# VCU.net
KiCad netlist of a schematic drawn in EAGLE
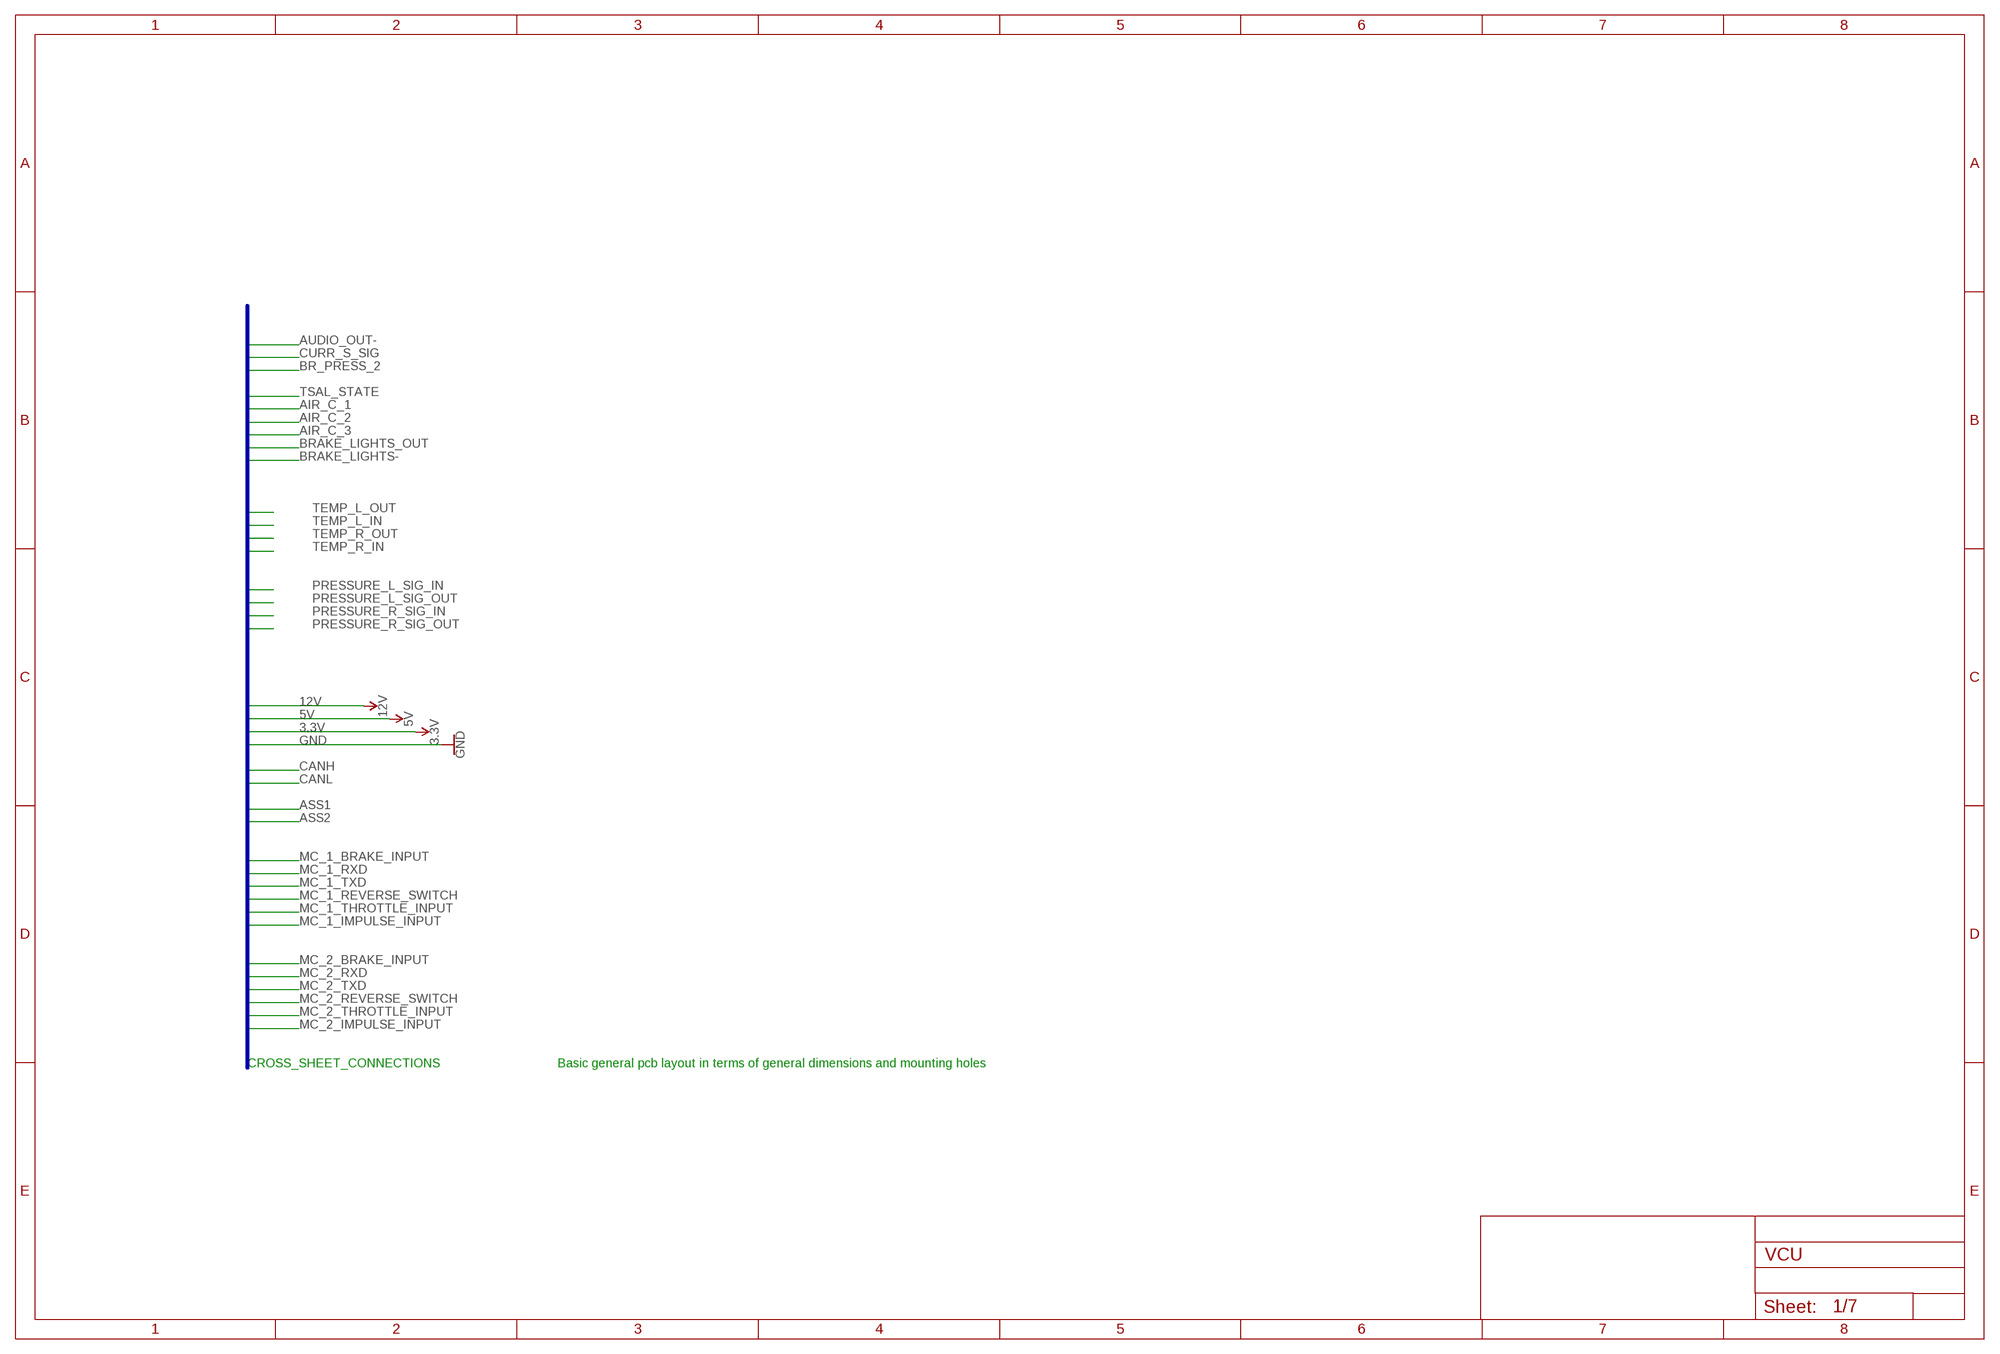
[diagram p0: schematic, sheet 1]
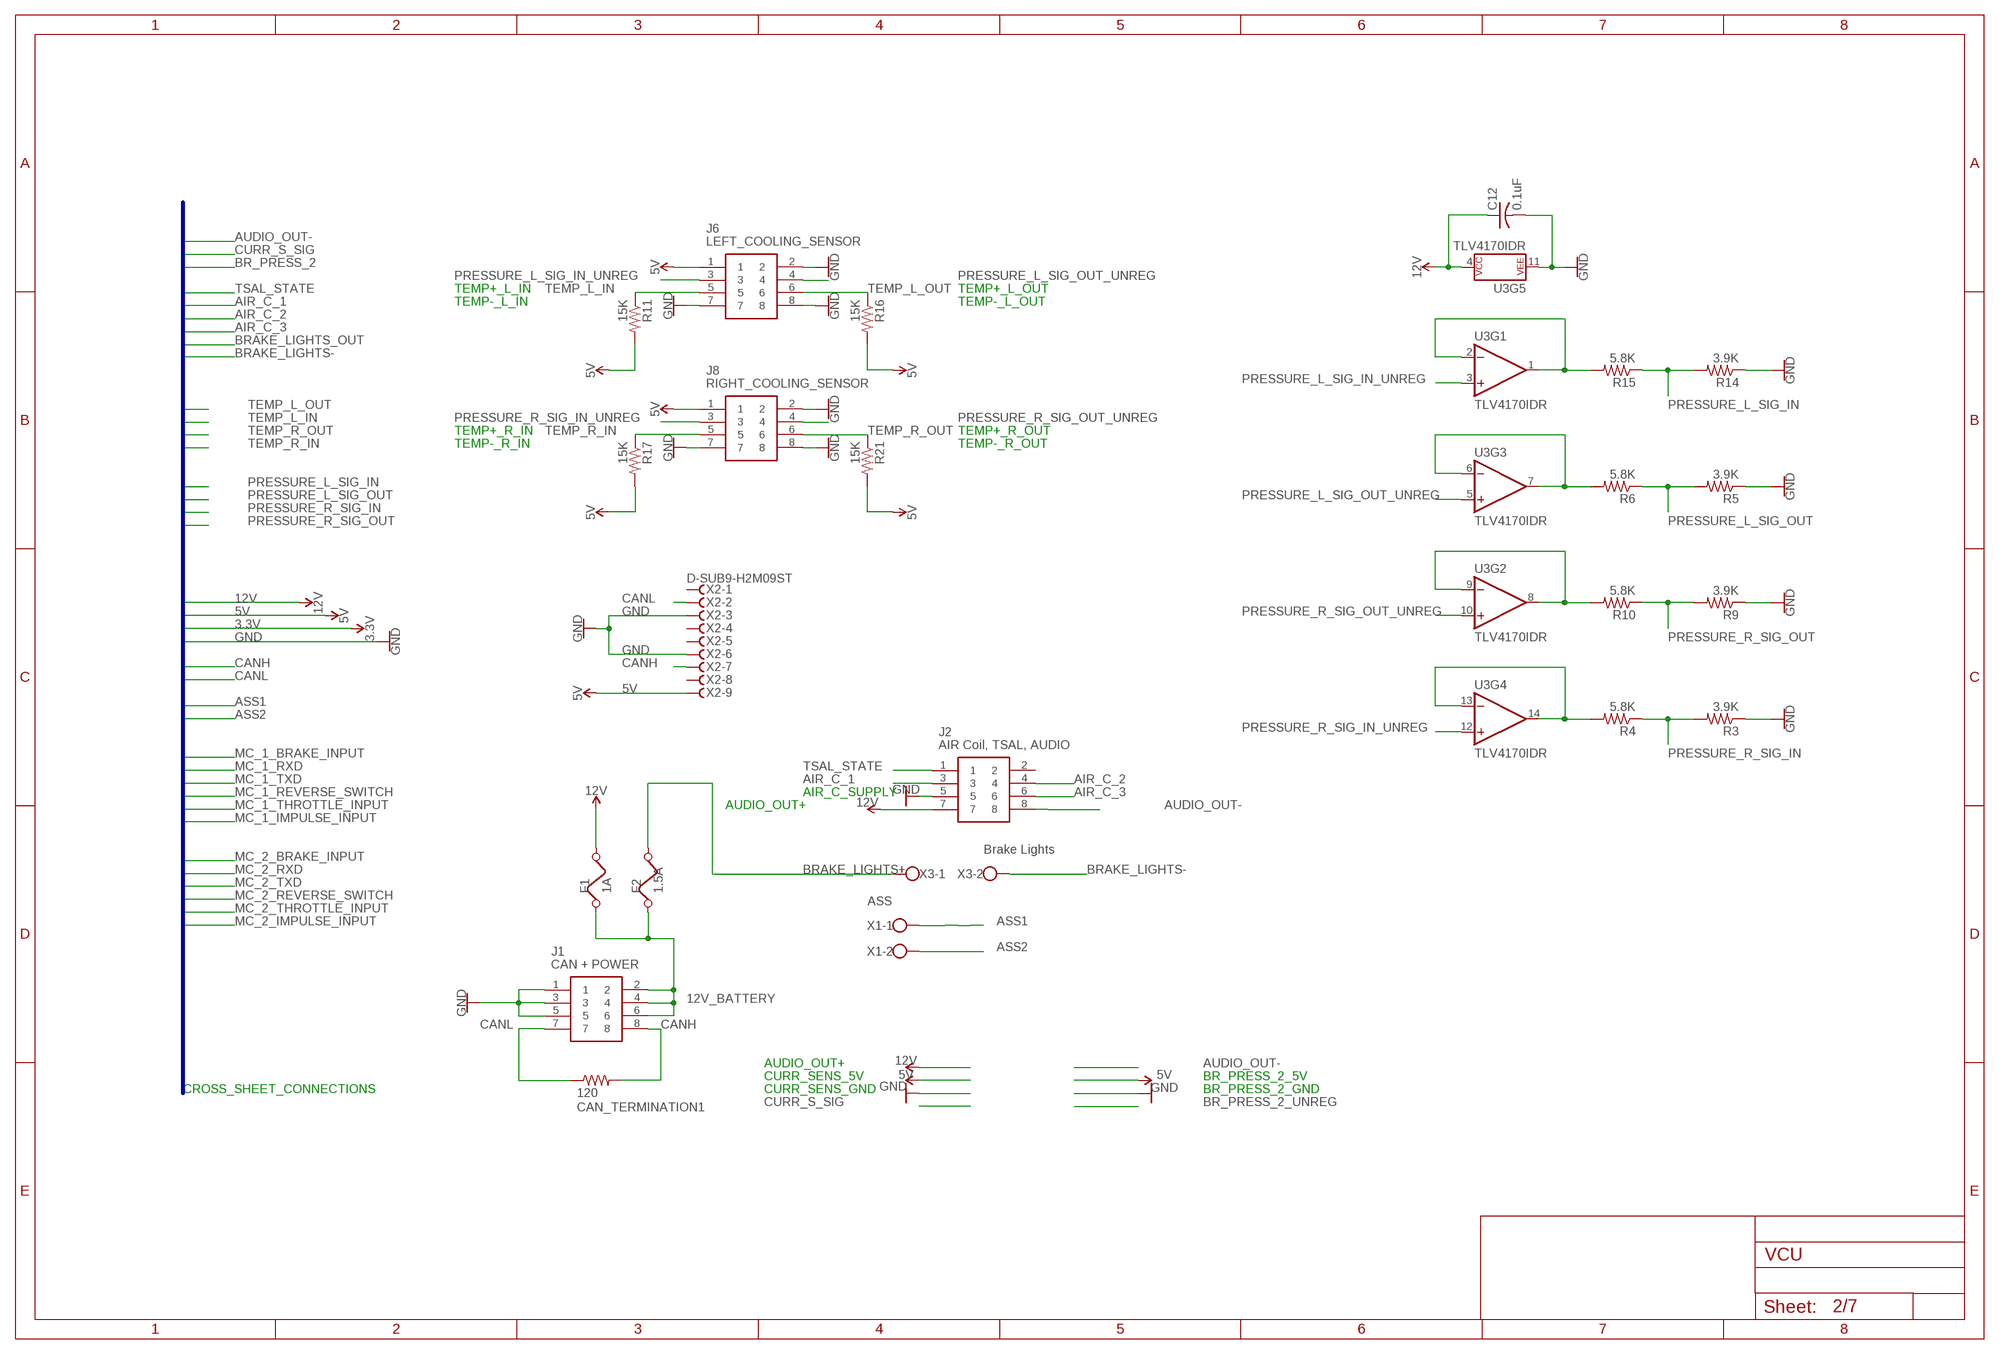
[diagram p1: schematic, sheet 2]
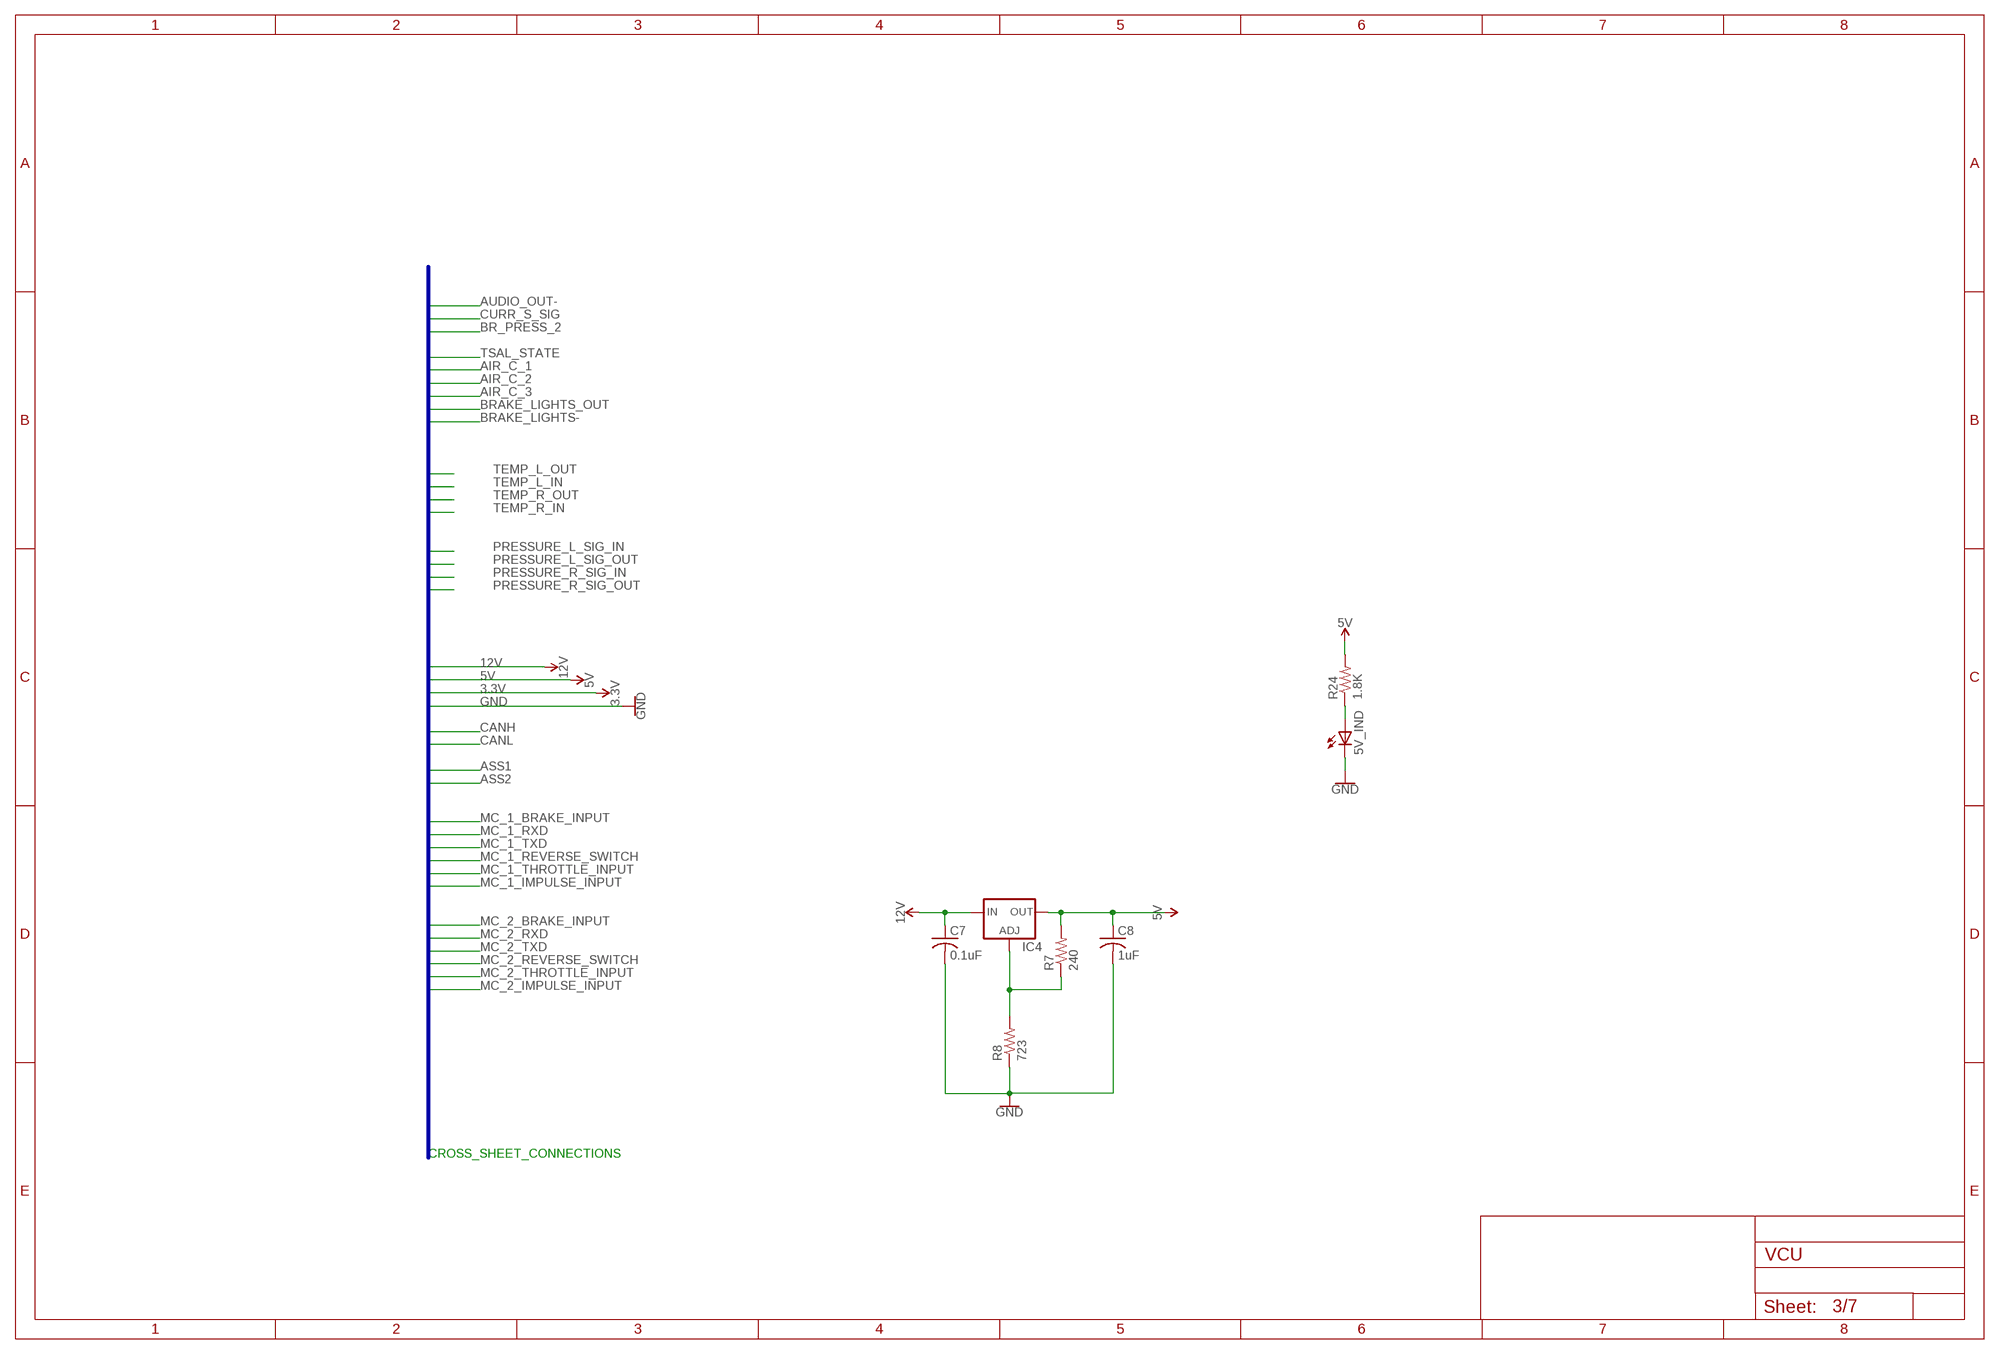
[diagram p2: schematic, sheet 3]
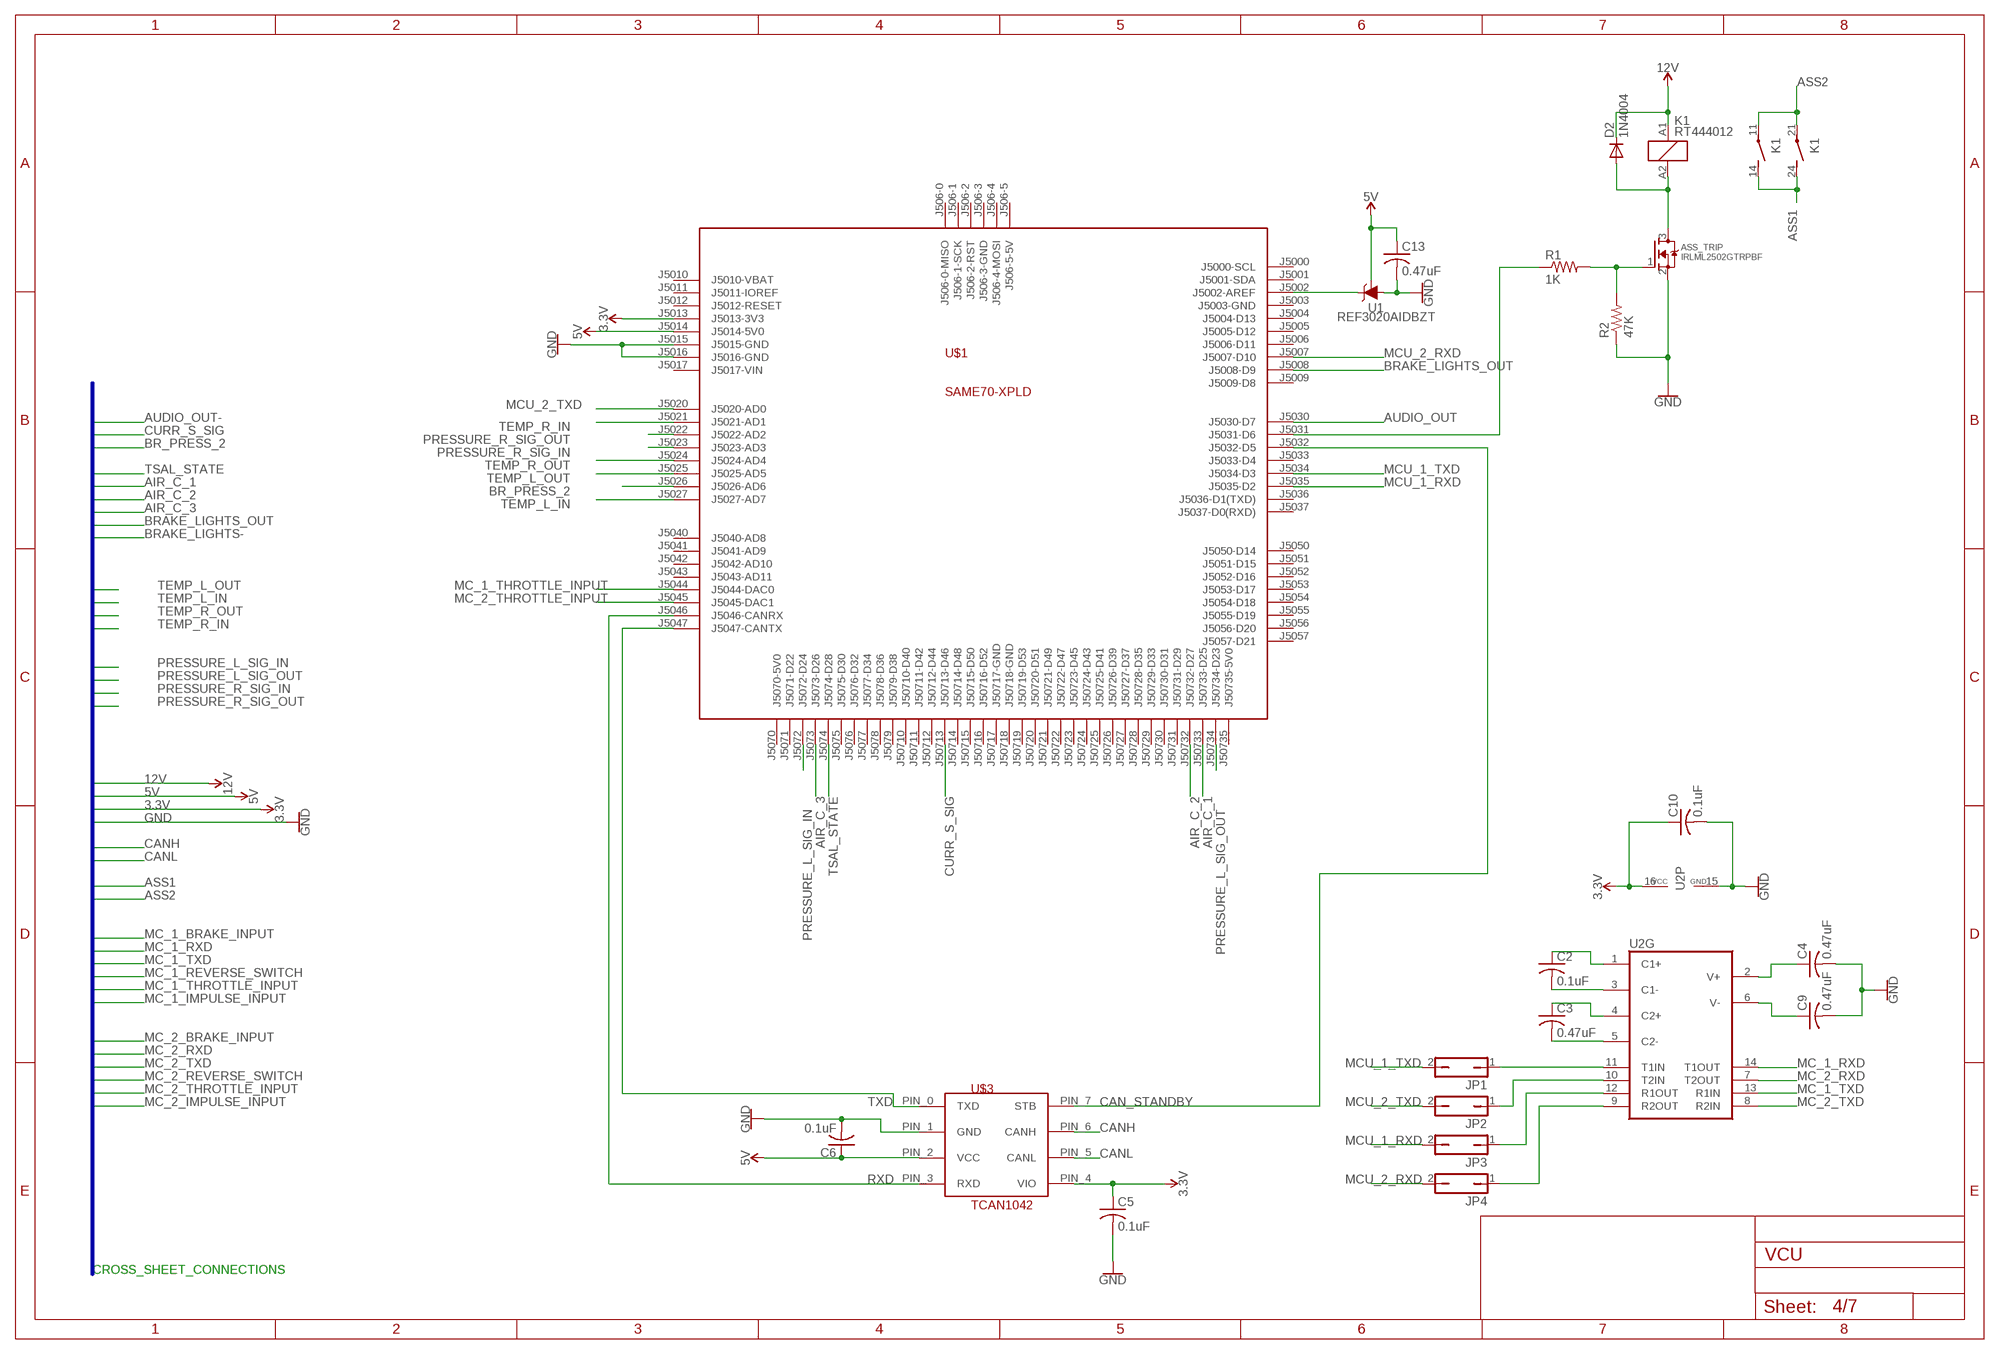
[diagram p3: schematic, sheet 4]
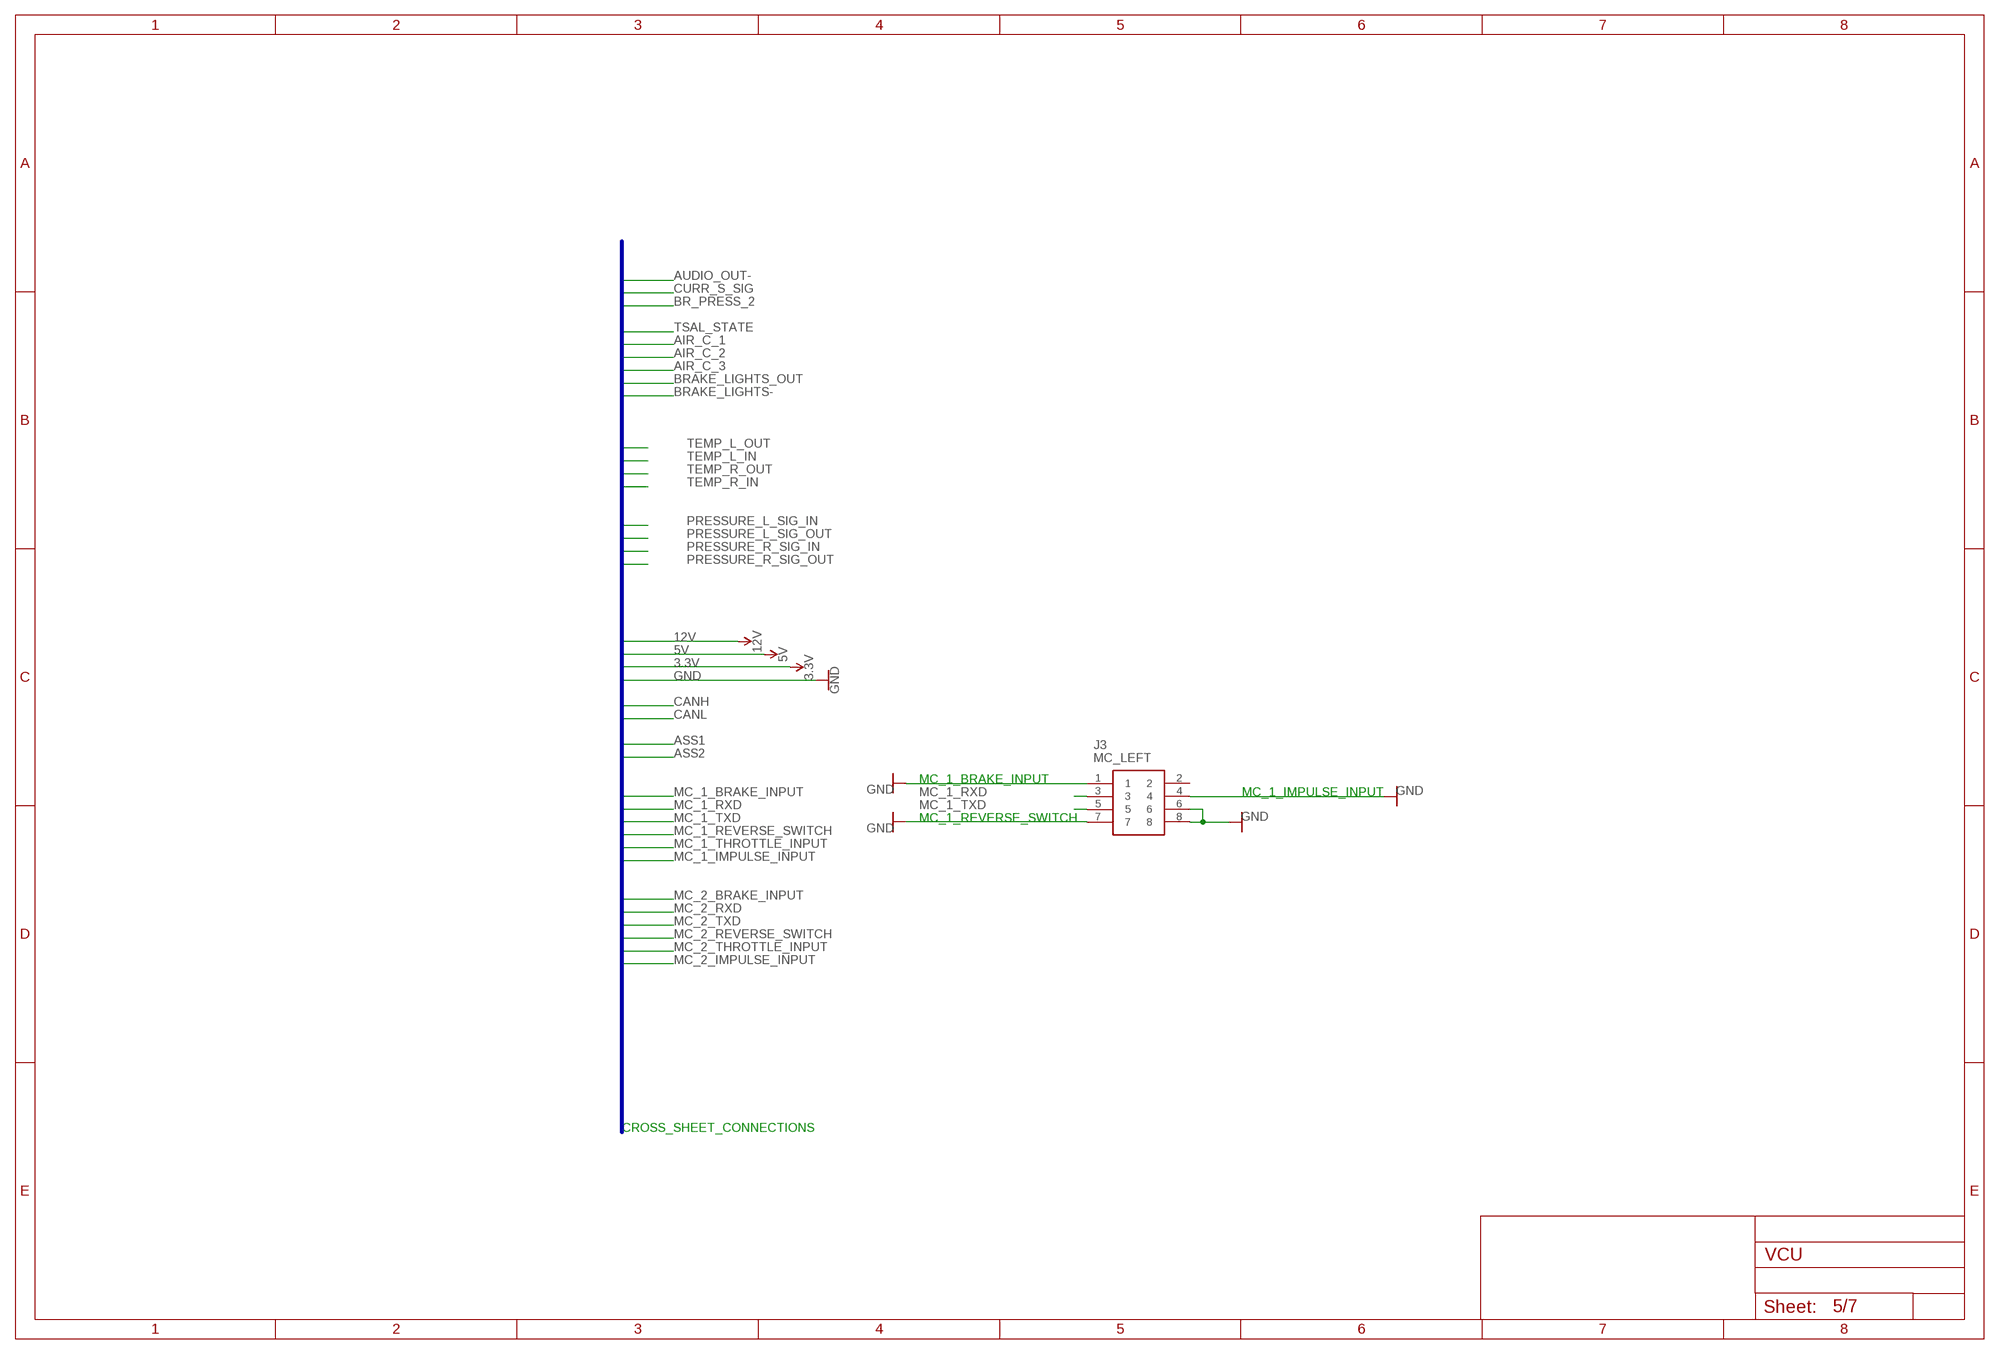
[diagram p4: schematic, sheet 5]
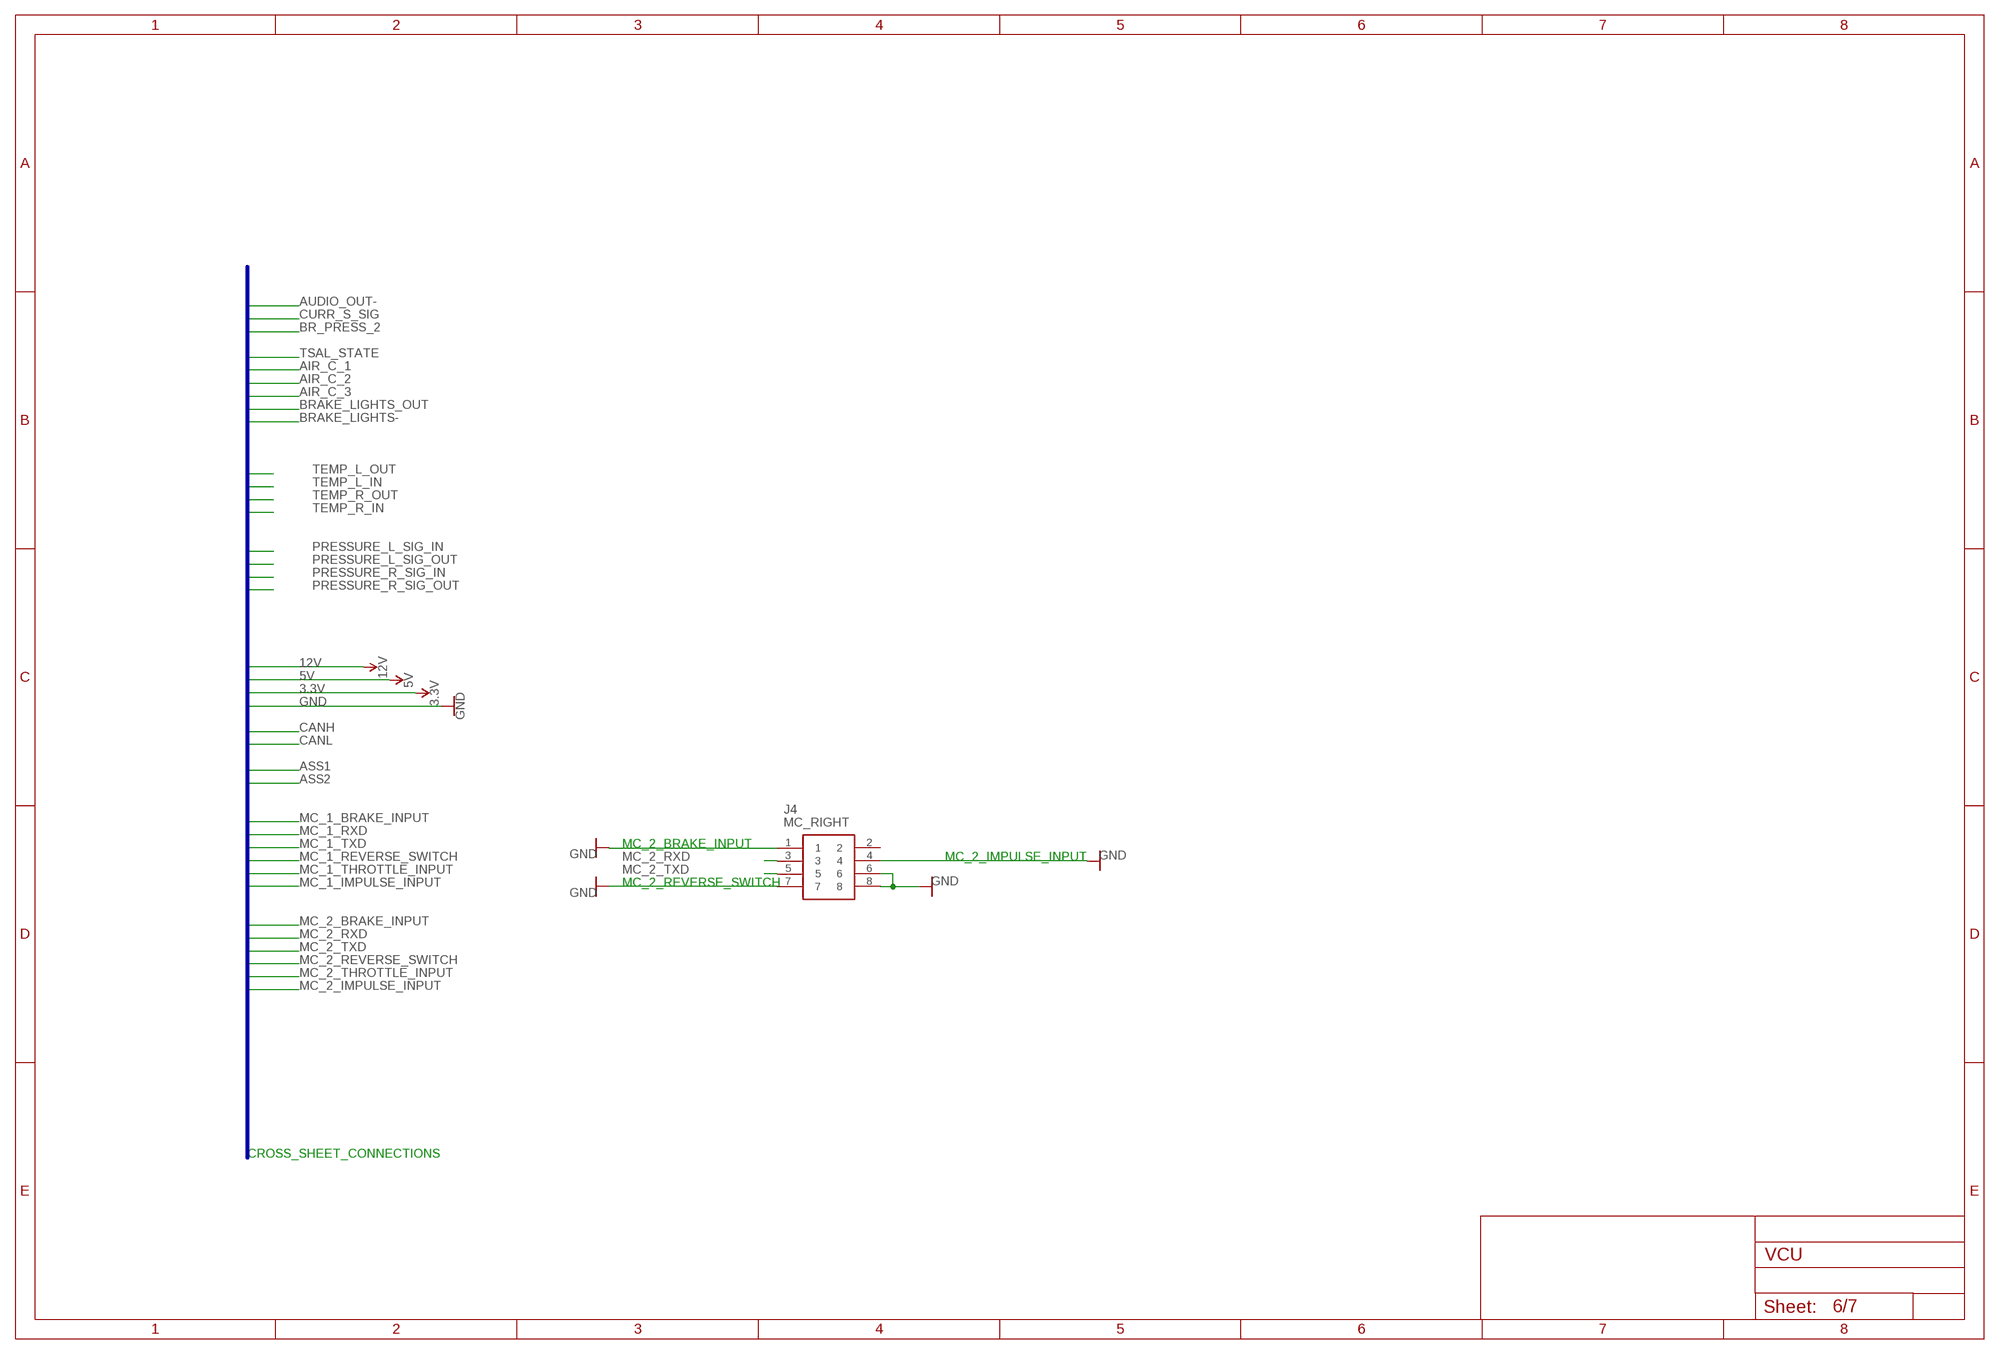
[diagram p5: schematic, sheet 6]
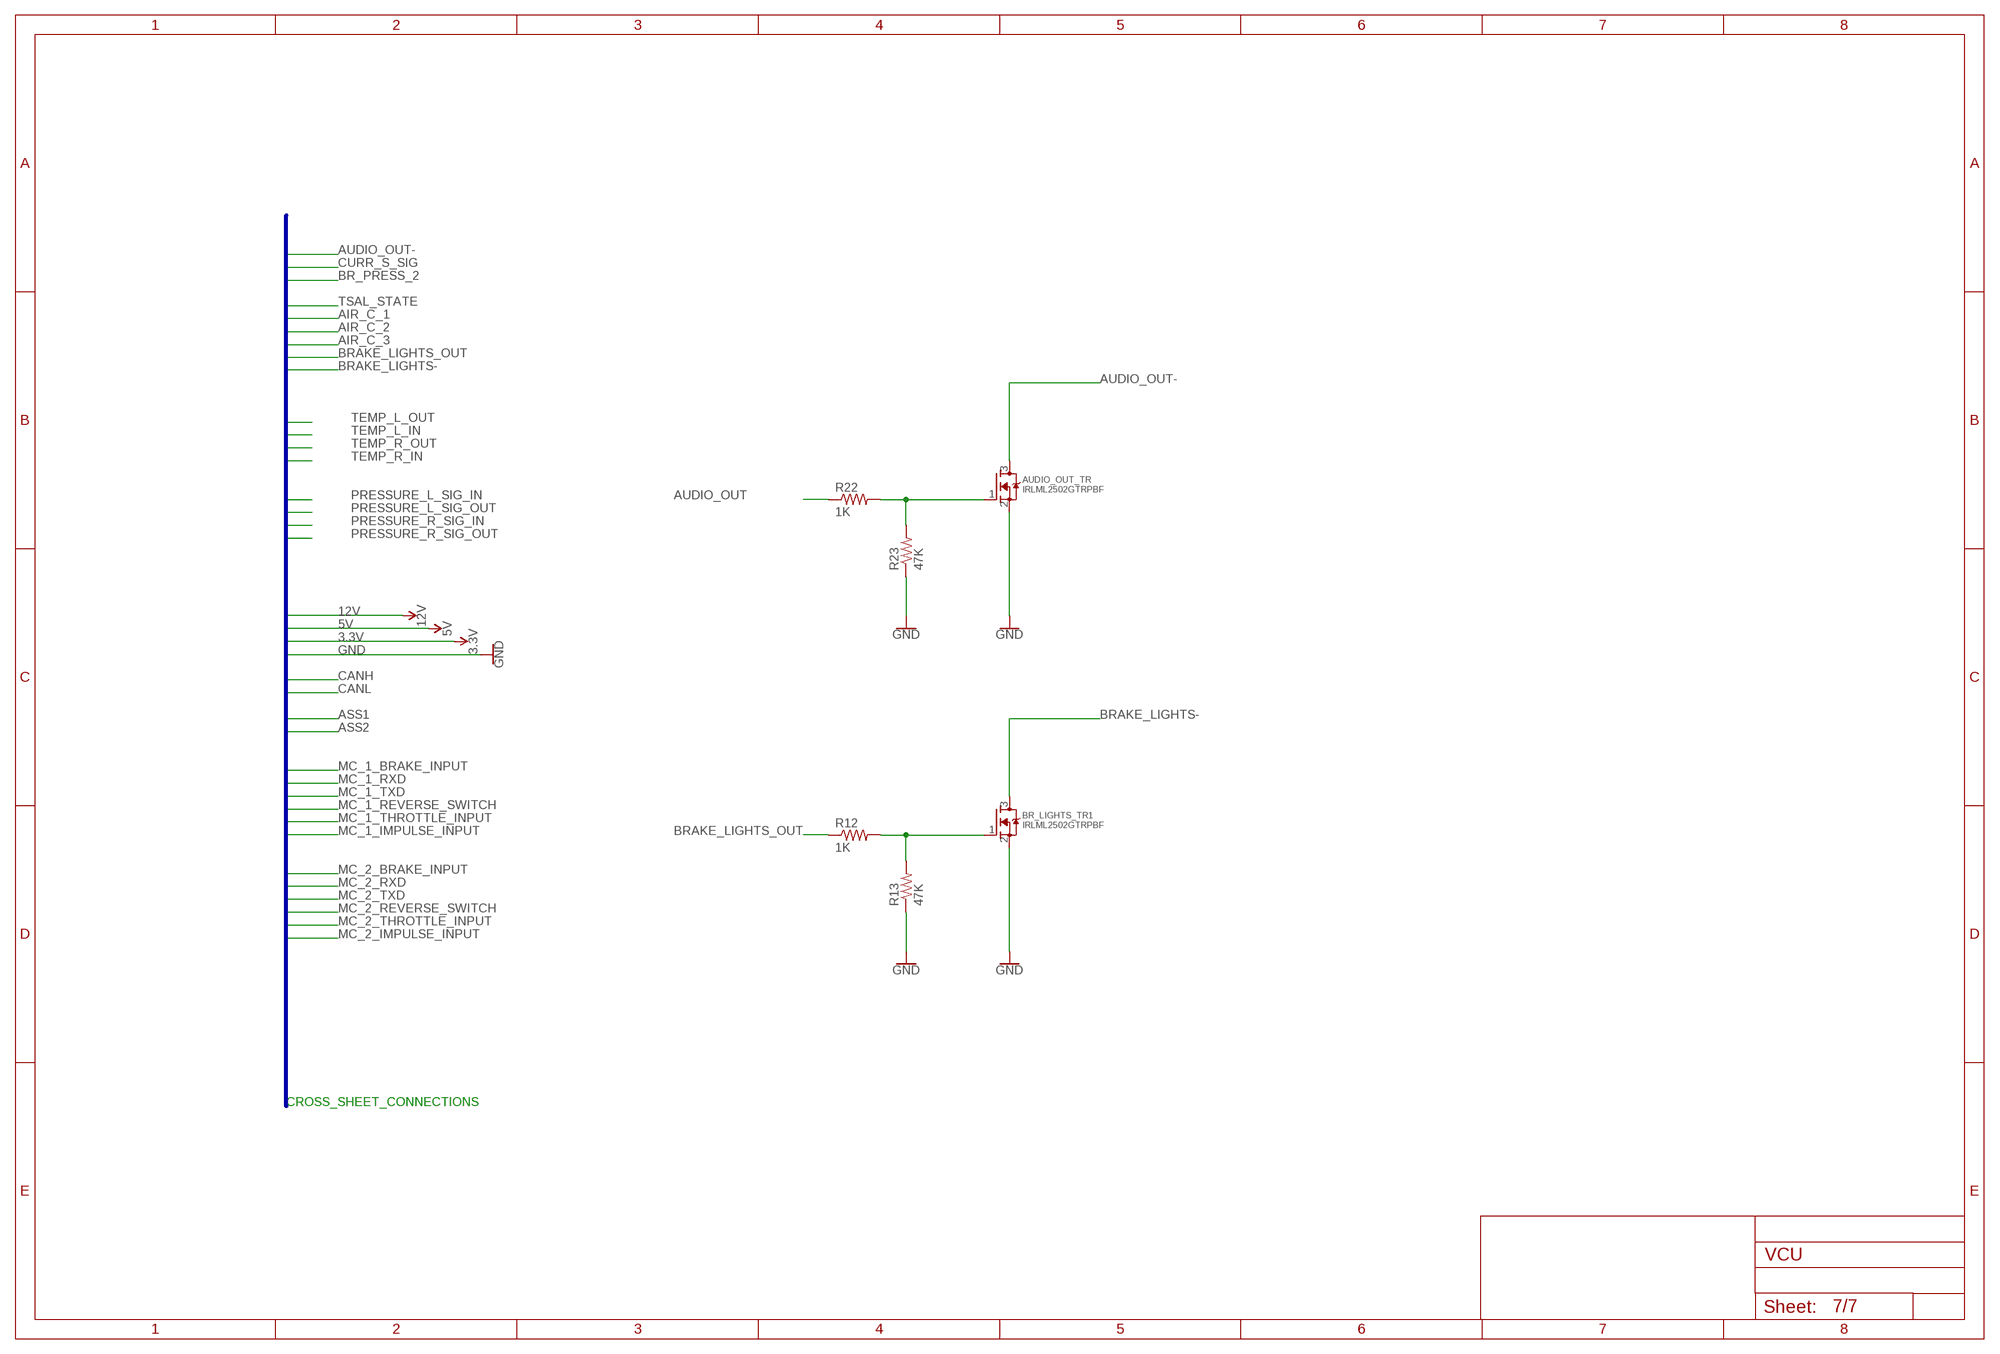
[diagram p6: schematic, sheet 7]

(export (version "E")
  (design (tool "Eeschema 10.0.6"))
  (components
    (comp (ref "ASS_TRIP")
      (value "IRLML2502GTRPBF")
      (footprint "eagle-import:SOT23")
      (libsource (lib "eagle-import") (part "MOSFET-NREFLOW"))
    )
    (comp (ref "C2")
      (value "0.1uF")
      (footprint "eagle-import:C025-024X044")
      (libsource (lib "eagle-import") (part "C-US025-024X044"))
    )
    (comp (ref "C3")
      (value "0.47uF")
      (footprint "eagle-import:C025-024X044")
      (libsource (lib "eagle-import") (part "C-US025-024X044"))
    )
    (comp (ref "C4")
      (value "0.47uF")
      (footprint "eagle-import:C025-024X044")
      (libsource (lib "eagle-import") (part "C-US025-024X044"))
    )
    (comp (ref "C5")
      (value "0.1uF")
      (footprint "eagle-import:C025-024X044")
      (libsource (lib "eagle-import") (part "C-US025-024X044"))
    )
    (comp (ref "C6")
      (value "0.1uF")
      (footprint "eagle-import:C025-024X044")
      (libsource (lib "eagle-import") (part "C-US025-024X044"))
    )
    (comp (ref "C9")
      (value "0.47uF")
      (footprint "eagle-import:C025-024X044")
      (libsource (lib "eagle-import") (part "C-US025-024X044"))
    )
    (comp (ref "C10")
      (value "0.1uF")
      (footprint "eagle-import:C025-024X044")
      (libsource (lib "eagle-import") (part "C-US025-024X044"))
    )
    (comp (ref "C13")
      (value "0.47uF")
      (footprint "eagle-import:C050-024X044")
      (libsource (lib "eagle-import") (part "C-US050-024X044"))
    )
    (comp (ref "D2")
      (value "1N4004")
      (footprint "eagle-import:DO41-10")
      (libsource (lib "eagle-import") (part "1N4004"))
    )
    (comp (ref "JP1")
      (value "JP1Q")
      (footprint "eagle-import:JP1")
      (libsource (lib "eagle-import") (part "JP1Q"))
    )
    (comp (ref "JP2")
      (value "JP1Q")
      (footprint "eagle-import:JP1")
      (libsource (lib "eagle-import") (part "JP1Q"))
    )
    (comp (ref "JP3")
      (value "JP1Q")
      (footprint "eagle-import:JP1")
      (libsource (lib "eagle-import") (part "JP1Q"))
    )
    (comp (ref "JP4")
      (value "JP1Q")
      (footprint "eagle-import:JP1")
      (libsource (lib "eagle-import") (part "JP1Q"))
    )
    (comp (ref "K1")
      (value "RT444012")
      (footprint "eagle-import:RT2N_O")
      (libsource (lib "eagle-import") (part "RT44?4012"))
    )
    (comp (ref "R1")
      (value "1K")
      (footprint "eagle-import:R0805")
      (libsource (lib "eagle-import") (part "R-US_R0805"))
    )
    (comp (ref "R2")
      (value "47K")
      (footprint "eagle-import:R0805")
      (libsource (lib "eagle-import") (part "R-US_R0805"))
    )
    (comp (ref "U$1")
      (value "SAME70-XPLD")
      (footprint "eagle-import:SAME70-XPLD")
      (libsource (lib "eagle-import") (part "SAME70-XPLD"))
    )
    (comp (ref "U$3")
      (value "TCAN1042")
      (footprint "eagle-import:TCAN1042")
      (libsource (lib "eagle-import") (part "TCAN1042"))
    )
    (comp (ref "U1")
      (value "REF3020AIDBZT")
      (footprint "eagle-import:SOT23-3")
      (libsource (lib "eagle-import") (part "LM4051"))
    )
    (comp (ref "U2")
      (value "MAX3232S")
      (footprint "eagle-import:SO16")
      (libsource (lib "eagle-import") (part "MAX3232S"))
    )
    (comp (ref "J4")
      (value "MC_RIGHT")
      (footprint "eagle-import:HDRV8W64P254_2X4_1778X895X915P")
      (fields
        (field (name "MANUFACTURER_PART_NUMBER") "T821108A1S100CEU")
        (field (name "RS_PART_NUMBER") "1702738")
      )
      (libsource (lib "eagle-import") (part "T821108A1S100CEU"))
    )
    (comp (ref "AUDIO_OUT_TR")
      (value "IRLML2502GTRPBF")
      (footprint "eagle-import:SOT23")
      (libsource (lib "eagle-import") (part "MOSFET-NREFLOW"))
    )
    (comp (ref "BR_LIGHTS_TR1")
      (value "IRLML2502GTRPBF")
      (footprint "eagle-import:SOT23")
      (libsource (lib "eagle-import") (part "MOSFET-NREFLOW"))
    )
    (comp (ref "R12")
      (value "1K")
      (footprint "eagle-import:R0805")
      (libsource (lib "eagle-import") (part "R-US_R0805"))
    )
    (comp (ref "R13")
      (value "47K")
      (footprint "eagle-import:R0805")
      (libsource (lib "eagle-import") (part "R-US_R0805"))
    )
    (comp (ref "R22")
      (value "1K")
      (footprint "eagle-import:R0805")
      (libsource (lib "eagle-import") (part "R-US_R0805"))
    )
    (comp (ref "R23")
      (value "47K")
      (footprint "eagle-import:R0805")
      (libsource (lib "eagle-import") (part "R-US_R0805"))
    )
    (comp (ref "J3")
      (value "MC_LEFT")
      (footprint "eagle-import:HDRV8W64P254_2X4_1778X895X915P")
      (fields
        (field (name "MANUFACTURER_PART_NUMBER") "T821108A1S100CEU")
        (field (name "RS_PART_NUMBER") "1702738")
      )
      (libsource (lib "eagle-import") (part "T821108A1S100CEU"))
    )
    (comp (ref "C12")
      (value "0.1uF")
      (footprint "eagle-import:C050-024X044")
      (libsource (lib "eagle-import") (part "C-US050-024X044"))
    )
    (comp (ref "CAN_TERMINATION1")
      (value "120")
      (footprint "eagle-import:R0805")
      (libsource (lib "eagle-import") (part "R-US_R0805"))
    )
    (comp (ref "F1")
      (value "1A")
      (footprint "eagle-import:FUSE")
      (libsource (lib "eagle-import") (part "FUSE"))
    )
    (comp (ref "F2")
      (value "1.5A")
      (footprint "eagle-import:FUSE")
      (libsource (lib "eagle-import") (part "FUSE"))
    )
    (comp (ref "J1")
      (value "CAN + POWER")
      (footprint "eagle-import:HDRV8W64P254_2X4_1778X895X915P")
      (fields
        (field (name "MANUFACTURER_PART_NUMBER") "T821108A1S100CEU")
        (field (name "RS_PART_NUMBER") "1702738")
      )
      (libsource (lib "eagle-import") (part "T821108A1S100CEU"))
    )
    (comp (ref "J2")
      (value "AIR Coil, TSAL, AUDIO")
      (footprint "eagle-import:HDRV8W64P254_2X4_1778X895X915P")
      (fields
        (field (name "MANUFACTURER_PART_NUMBER") "T821108A1S100CEU")
        (field (name "RS_PART_NUMBER") "1702738")
      )
      (libsource (lib "eagle-import") (part "T821108A1S100CEU"))
    )
    (comp (ref "J6")
      (value "LEFT_COOLING_SENSOR")
      (footprint "eagle-import:HDRV8W64P254_2X4_1778X895X915P")
      (fields
        (field (name "MANUFACTURER_PART_NUMBER") "T821108A1S100CEU")
        (field (name "RS_PART_NUMBER") "1702738")
      )
      (libsource (lib "eagle-import") (part "T821108A1S100CEU"))
    )
    (comp (ref "J8")
      (value "RIGHT_COOLING_SENSOR")
      (footprint "eagle-import:HDRV8W64P254_2X4_1778X895X915P")
      (fields
        (field (name "MANUFACTURER_PART_NUMBER") "T821108A1S100CEU")
        (field (name "RS_PART_NUMBER") "1702738")
      )
      (libsource (lib "eagle-import") (part "T821108A1S100CEU"))
    )
    (comp (ref "R3")
      (value "3.9K")
      (footprint "eagle-import:R0805")
      (libsource (lib "eagle-import") (part "R-US_R0805"))
    )
    (comp (ref "R4")
      (value "5.8K")
      (footprint "eagle-import:R0805")
      (libsource (lib "eagle-import") (part "R-US_R0805"))
    )
    (comp (ref "R5")
      (value "3.9K")
      (footprint "eagle-import:R0805")
      (libsource (lib "eagle-import") (part "R-US_R0805"))
    )
    (comp (ref "R6")
      (value "5.8K")
      (footprint "eagle-import:R0805")
      (libsource (lib "eagle-import") (part "R-US_R0805"))
    )
    (comp (ref "R9")
      (value "3.9K")
      (footprint "eagle-import:R0805")
      (libsource (lib "eagle-import") (part "R-US_R0805"))
    )
    (comp (ref "R10")
      (value "5.8K")
      (footprint "eagle-import:R0805")
      (libsource (lib "eagle-import") (part "R-US_R0805"))
    )
    (comp (ref "R11")
      (value "15K")
      (footprint "eagle-import:R0805")
      (libsource (lib "eagle-import") (part "R-US_R0805"))
    )
    (comp (ref "R14")
      (value "3.9K")
      (footprint "eagle-import:R0805")
      (libsource (lib "eagle-import") (part "R-US_R0805"))
    )
    (comp (ref "R15")
      (value "5.8K")
      (footprint "eagle-import:R0805")
      (libsource (lib "eagle-import") (part "R-US_R0805"))
    )
    (comp (ref "R16")
      (value "15K")
      (footprint "eagle-import:R0805")
      (libsource (lib "eagle-import") (part "R-US_R0805"))
    )
    (comp (ref "R17")
      (value "15K")
      (footprint "eagle-import:R0805")
      (libsource (lib "eagle-import") (part "R-US_R0805"))
    )
    (comp (ref "R21")
      (value "15K")
      (footprint "eagle-import:R0805")
      (libsource (lib "eagle-import") (part "R-US_R0805"))
    )
    (comp (ref "U3")
      (value "TLV4170IDR")
      (footprint "eagle-import:SO14")
      (libsource (lib "eagle-import") (part "LMV324"))
    )
    (comp (ref "X1")
      (value "ASS")
      (footprint "eagle-import:W237-102")
      (fields (field (name "MPN") "237-102"))
      (libsource (lib "eagle-import") (part "W237-102"))
    )
    (comp (ref "X2")
      (value "D-SUB9-H2M09ST")
      (footprint "eagle-import:H2M09ST")
      (libsource (lib "eagle-import") (part "D-SUB9-H2M09ST"))
    )
    (comp (ref "X3")
      (value "Brake Lights")
      (footprint "eagle-import:W237-102")
      (fields (field (name "MPN") "237-102"))
      (libsource (lib "eagle-import") (part "W237-102"))
    )
    (comp (ref "5V_IND")
      (value "LED3MM")
      (footprint "eagle-import:LED3MM")
      (libsource (lib "eagle-import") (part "LED3MM"))
    )
    (comp (ref "C7")
      (value "0.1uF")
      (footprint "eagle-import:C050-025X075")
      (libsource (lib "eagle-import") (part "C-US050-025X075"))
    )
    (comp (ref "C8")
      (value "1uF")
      (footprint "eagle-import:C050-025X075")
      (libsource (lib "eagle-import") (part "C-US050-025X075"))
    )
    (comp (ref "IC4")
      (value "LM317TS")
      (footprint "eagle-import:317TS")
      (libsource (lib "eagle-import") (part "LM317TS"))
    )
    (comp (ref "R7")
      (value "240")
      (footprint "eagle-import:R0805")
      (libsource (lib "eagle-import") (part "R-US_R0805"))
    )
    (comp (ref "R8")
      (value "723")
      (footprint "eagle-import:R0805")
      (libsource (lib "eagle-import") (part "R-US_R0805"))
    )
    (comp (ref "R24")
      (value "1.8K")
      (footprint "eagle-import:R0805")
      (libsource (lib "eagle-import") (part "R-US_R0805"))
    )
  )
  (nets
    (net (code "1") (name "3.3V") (class "Default")
      (node (ref "C10") (pin "1") (pinfunction "1_1") (pintype "passive"))
      (node (ref "C5") (pin "1") (pinfunction "1_1") (pintype "passive"))
      (node (ref "U$1") (pin "J5013") (pinfunction "J5013-3V3_J5013") (pintype "bidirectional"))
      (node (ref "U$3") (pin "PIN_4") (pinfunction "VIO_PIN_4") (pintype "bidirectional"))
      (node (ref "U2") (pin "16") (pinfunction "VCC_16") (pintype "power_in"))
    )
    (net (code "2") (name "5V") (class "Default")
      (node (ref "C13") (pin "1") (pinfunction "1_1") (pintype "passive"))
      (node (ref "C6") (pin "1") (pinfunction "1_1") (pintype "passive"))
      (node (ref "C8") (pin "1") (pinfunction "1_1") (pintype "passive"))
      (node (ref "IC4") (pin "2") (pinfunction "OUT_2") (pintype "passive"))
      (node (ref "J6") (pin "1") (pinfunction "1_1") (pintype "bidirectional"))
      (node (ref "J8") (pin "1") (pinfunction "1_1") (pintype "bidirectional"))
      (node (ref "R11") (pin "2") (pinfunction "2_2") (pintype "passive"))
      (node (ref "R16") (pin "2") (pinfunction "2_2") (pintype "passive"))
      (node (ref "R17") (pin "2") (pinfunction "2_2") (pintype "passive"))
      (node (ref "R21") (pin "2") (pinfunction "2_2") (pintype "passive"))
      (node (ref "R24") (pin "2") (pinfunction "2_2") (pintype "passive"))
      (node (ref "R7") (pin "2") (pinfunction "2_2") (pintype "passive"))
      (node (ref "U$1") (pin "J5014") (pinfunction "J5014-5V0_J5014") (pintype "bidirectional"))
      (node (ref "U$3") (pin "PIN_2") (pinfunction "VCC_PIN_2") (pintype "bidirectional"))
      (node (ref "U1") (pin "1") (pinfunction "ADJ_1") (pintype "bidirectional"))
      (node (ref "X2") (pin "9") (pinfunction "F_9") (pintype "passive"))
    )
    (net (code "3") (name "12V") (class "Default")
      (node (ref "C12") (pin "1") (pinfunction "1_1") (pintype "passive"))
      (node (ref "C7") (pin "1") (pinfunction "1_1") (pintype "passive"))
      (node (ref "D2") (pin "C") (pinfunction "C_C") (pintype "passive"))
      (node (ref "F1") (pin "2") (pinfunction "2_2") (pintype "passive"))
      (node (ref "IC4") (pin "3") (pinfunction "IN_3") (pintype "input"))
      (node (ref "J2") (pin "7") (pinfunction "7_7") (pintype "bidirectional"))
      (node (ref "K1") (pin "A1") (pinfunction "1_A1") (pintype "passive"))
      (node (ref "U3") (pin "4") (pinfunction "P$V+_4") (pintype "bidirectional"))
    )
    (net (code "4") (name "12V_BATTERY") (class "Default")
      (node (ref "F1") (pin "1") (pinfunction "1_1") (pintype "passive"))
      (node (ref "F2") (pin "1") (pinfunction "1_1") (pintype "passive"))
      (node (ref "J1") (pin "2") (pinfunction "2_2") (pintype "bidirectional"))
      (node (ref "J1") (pin "4") (pinfunction "4_4") (pintype "bidirectional"))
      (node (ref "J1") (pin "6") (pinfunction "6_6") (pintype "bidirectional"))
    )
    (net (code "5") (name "AIR_C_1") (class "Default")
      (node (ref "J2") (pin "3") (pinfunction "3_3") (pintype "bidirectional"))
      (node (ref "U$1") (pin "J50733") (pinfunction "J50733-D25_J50733") (pintype "bidirectional"))
    )
    (net (code "6") (name "AIR_C_2") (class "Default")
      (node (ref "J2") (pin "4") (pinfunction "4_4") (pintype "bidirectional"))
      (node (ref "U$1") (pin "J50732") (pinfunction "J50732-D27_J50732") (pintype "bidirectional"))
    )
    (net (code "7") (name "AIR_C_3") (class "Default")
      (node (ref "J2") (pin "6") (pinfunction "6_6") (pintype "bidirectional"))
      (node (ref "U$1") (pin "J5073") (pinfunction "J5073-D26_J5073") (pintype "bidirectional"))
    )
    (net (code "8") (name "ASS1") (class "Default")
      (node (ref "K1") (pin "14") (pinfunction "S_14") (pintype "passive"))
      (node (ref "K1") (pin "24") (pinfunction "S_24") (pintype "passive"))
      (node (ref "X1") (pin "1") (pinfunction "KL_1") (pintype "passive"))
    )
    (net (code "9") (name "ASS2") (class "Default")
      (node (ref "K1") (pin "11") (pinfunction "P_11") (pintype "passive"))
      (node (ref "K1") (pin "21") (pinfunction "P_21") (pintype "passive"))
      (node (ref "X1") (pin "2") (pinfunction "KL_2") (pintype "passive"))
    )
    (net (code "10") (name "AUDIO_OUT") (class "Default")
      (node (ref "R22") (pin "1") (pinfunction "1_1") (pintype "passive"))
      (node (ref "U$1") (pin "J5030") (pinfunction "J5030-D7_J5030") (pintype "bidirectional"))
    )
    (net (code "11") (name "AUDIO_OUT-") (class "Default")
      (node (ref "AUDIO_OUT_TR") (pin "3") (pinfunction "D_3") (pintype "bidirectional"))
      (node (ref "J2") (pin "8") (pinfunction "8_8") (pintype "bidirectional"))
    )
    (net (code "12") (name "BRAKE_LIGHTS+") (class "Default")
      (node (ref "F2") (pin "2") (pinfunction "2_2") (pintype "passive"))
      (node (ref "X3") (pin "1") (pinfunction "KL_1") (pintype "passive"))
    )
    (net (code "13") (name "BRAKE_LIGHTS-") (class "Default")
      (node (ref "BR_LIGHTS_TR1") (pin "3") (pinfunction "D_3") (pintype "bidirectional"))
      (node (ref "X3") (pin "2") (pinfunction "KL_2") (pintype "passive"))
    )
    (net (code "14") (name "BRAKE_LIGHTS_OUT") (class "Default")
      (node (ref "R12") (pin "1") (pinfunction "1_1") (pintype "passive"))
      (node (ref "U$1") (pin "J5008") (pinfunction "J5008-D9_J5008") (pintype "bidirectional"))
    )
    (net (code "15") (name "BR_PRESS_2") (class "Default")
      (node (ref "U$1") (pin "J5026") (pinfunction "J5026-AD6_J5026") (pintype "bidirectional"))
    )
    (net (code "17") (name "CANH") (class "Default")
      (node (ref "CAN_TERMINATION1") (pin "2") (pinfunction "2_2") (pintype "passive"))
      (node (ref "J1") (pin "8") (pinfunction "8_8") (pintype "bidirectional"))
      (node (ref "U$3") (pin "PIN_6") (pinfunction "CANH_PIN_6") (pintype "bidirectional"))
      (node (ref "X2") (pin "7") (pinfunction "F_7") (pintype "passive"))
    )
    (net (code "18") (name "CANL") (class "Default")
      (node (ref "CAN_TERMINATION1") (pin "1") (pinfunction "1_1") (pintype "passive"))
      (node (ref "J1") (pin "7") (pinfunction "7_7") (pintype "bidirectional"))
      (node (ref "U$3") (pin "PIN_5") (pinfunction "CANL_PIN_5") (pintype "bidirectional"))
      (node (ref "X2") (pin "2") (pinfunction "F_2") (pintype "passive"))
    )
    (net (code "19") (name "CAN_STANDBY") (class "Default")
      (node (ref "U$1") (pin "J5032") (pinfunction "J5032-D5_J5032") (pintype "bidirectional"))
      (node (ref "U$3") (pin "PIN_7") (pinfunction "STB_PIN_7") (pintype "bidirectional"))
    )
    (net (code "20") (name "CURR_S_SIG") (class "Default")
      (node (ref "U$1") (pin "J50713") (pinfunction "J50713-D46_J50713") (pintype "bidirectional"))
    )
    (net (code "21") (name "GND") (class "Default")
      (node (ref "5V_IND") (pin "K") (pinfunction "C_K") (pintype "passive"))
      (node (ref "ASS_TRIP") (pin "2") (pinfunction "S_2") (pintype "bidirectional"))
      (node (ref "AUDIO_OUT_TR") (pin "2") (pinfunction "S_2") (pintype "bidirectional"))
      (node (ref "BR_LIGHTS_TR1") (pin "2") (pinfunction "S_2") (pintype "bidirectional"))
      (node (ref "C10") (pin "2") (pinfunction "2_2") (pintype "passive"))
      (node (ref "C12") (pin "2") (pinfunction "2_2") (pintype "passive"))
      (node (ref "C13") (pin "2") (pinfunction "2_2") (pintype "passive"))
      (node (ref "C4") (pin "2") (pinfunction "2_2") (pintype "passive"))
      (node (ref "C5") (pin "2") (pinfunction "2_2") (pintype "passive"))
      (node (ref "C6") (pin "2") (pinfunction "2_2") (pintype "passive"))
      (node (ref "C7") (pin "2") (pinfunction "2_2") (pintype "passive"))
      (node (ref "C8") (pin "2") (pinfunction "2_2") (pintype "passive"))
      (node (ref "C9") (pin "2") (pinfunction "2_2") (pintype "passive"))
      (node (ref "J1") (pin "1") (pinfunction "1_1") (pintype "bidirectional"))
      (node (ref "J1") (pin "3") (pinfunction "3_3") (pintype "bidirectional"))
      (node (ref "J1") (pin "5") (pinfunction "5_5") (pintype "bidirectional"))
      (node (ref "J2") (pin "5") (pinfunction "5_5") (pintype "bidirectional"))
      (node (ref "J3") (pin "1") (pinfunction "1_1") (pintype "bidirectional"))
      (node (ref "J3") (pin "4") (pinfunction "4_4") (pintype "bidirectional"))
      (node (ref "J3") (pin "6") (pinfunction "6_6") (pintype "bidirectional"))
      (node (ref "J3") (pin "7") (pinfunction "7_7") (pintype "bidirectional"))
      (node (ref "J3") (pin "8") (pinfunction "8_8") (pintype "bidirectional"))
      (node (ref "J4") (pin "1") (pinfunction "1_1") (pintype "bidirectional"))
      (node (ref "J4") (pin "4") (pinfunction "4_4") (pintype "bidirectional"))
      (node (ref "J4") (pin "6") (pinfunction "6_6") (pintype "bidirectional"))
      (node (ref "J4") (pin "7") (pinfunction "7_7") (pintype "bidirectional"))
      (node (ref "J4") (pin "8") (pinfunction "8_8") (pintype "bidirectional"))
      (node (ref "J6") (pin "2") (pinfunction "2_2") (pintype "bidirectional"))
      (node (ref "J6") (pin "7") (pinfunction "7_7") (pintype "bidirectional"))
      (node (ref "J6") (pin "8") (pinfunction "8_8") (pintype "bidirectional"))
      (node (ref "J8") (pin "2") (pinfunction "2_2") (pintype "bidirectional"))
      (node (ref "J8") (pin "7") (pinfunction "7_7") (pintype "bidirectional"))
      (node (ref "J8") (pin "8") (pinfunction "8_8") (pintype "bidirectional"))
      (node (ref "R13") (pin "1") (pinfunction "1_1") (pintype "passive"))
      (node (ref "R14") (pin "1") (pinfunction "1_1") (pintype "passive"))
      (node (ref "R2") (pin "1") (pinfunction "1_1") (pintype "passive"))
      (node (ref "R23") (pin "1") (pinfunction "1_1") (pintype "passive"))
      (node (ref "R3") (pin "1") (pinfunction "1_1") (pintype "passive"))
      (node (ref "R5") (pin "1") (pinfunction "1_1") (pintype "passive"))
      (node (ref "R8") (pin "1") (pinfunction "1_1") (pintype "passive"))
      (node (ref "R9") (pin "1") (pinfunction "1_1") (pintype "passive"))
      (node (ref "U$1") (pin "J5015") (pinfunction "J5015-GND_J5015") (pintype "bidirectional"))
      (node (ref "U$1") (pin "J5016") (pinfunction "J5016-GND_J5016") (pintype "bidirectional"))
      (node (ref "U$3") (pin "PIN_1") (pinfunction "GND_PIN_1") (pintype "bidirectional"))
      (node (ref "U1") (pin "3") (pinfunction "A_3") (pintype "passive"))
      (node (ref "U2") (pin "15") (pinfunction "GND_15") (pintype "power_in"))
      (node (ref "U3") (pin "11") (pinfunction "P$V-_11") (pintype "bidirectional"))
      (node (ref "X2") (pin "3") (pinfunction "F_3") (pintype "passive"))
      (node (ref "X2") (pin "6") (pinfunction "F_6") (pintype "passive"))
    )
    (net (code "22") (name "MCU_1_RXD") (class "Default")
      (node (ref "JP3") (pin "2") (pinfunction "2_2") (pintype "passive"))
      (node (ref "U$1") (pin "J5035") (pinfunction "J5035-D2_J5035") (pintype "bidirectional"))
    )
    (net (code "23") (name "MCU_1_TXD") (class "Default")
      (node (ref "JP1") (pin "2") (pinfunction "2_2") (pintype "passive"))
      (node (ref "U$1") (pin "J5034") (pinfunction "J5034-D3_J5034") (pintype "bidirectional"))
    )
    (net (code "24") (name "MCU_2_RXD") (class "Default")
      (node (ref "JP4") (pin "2") (pinfunction "2_2") (pintype "passive"))
      (node (ref "U$1") (pin "J5007") (pinfunction "J5007-D10_J5007") (pintype "bidirectional"))
    )
    (net (code "25") (name "MCU_2_TXD") (class "Default")
      (node (ref "JP2") (pin "2") (pinfunction "2_2") (pintype "passive"))
      (node (ref "U$1") (pin "J5020") (pinfunction "J5020-AD0_J5020") (pintype "bidirectional"))
    )
    (net (code "29") (name "MC_1_RXD") (class "Default")
      (node (ref "J3") (pin "3") (pinfunction "3_3") (pintype "bidirectional"))
      (node (ref "U2") (pin "14") (pinfunction "T1OUT_14") (pintype "output"))
    )
    (net (code "30") (name "MC_1_THROTTLE_INPUT") (class "Default")
      (node (ref "U$1") (pin "J5044") (pinfunction "J5044-DAC0_J5044") (pintype "bidirectional"))
    )
    (net (code "31") (name "MC_1_TXD") (class "Default")
      (node (ref "J3") (pin "5") (pinfunction "5_5") (pintype "bidirectional"))
      (node (ref "U2") (pin "13") (pinfunction "R1IN_13") (pintype "input"))
    )
    (net (code "35") (name "MC_2_RXD") (class "Default")
      (node (ref "J4") (pin "3") (pinfunction "3_3") (pintype "bidirectional"))
      (node (ref "U2") (pin "7") (pinfunction "T2OUT_7") (pintype "output"))
    )
    (net (code "36") (name "MC_2_THROTTLE_INPUT") (class "Default")
      (node (ref "U$1") (pin "J5045") (pinfunction "J5045-DAC1_J5045") (pintype "bidirectional"))
    )
    (net (code "37") (name "MC_2_TXD") (class "Default")
      (node (ref "J4") (pin "5") (pinfunction "5_5") (pintype "bidirectional"))
      (node (ref "U2") (pin "8") (pinfunction "R2IN_8") (pintype "input"))
    )
    (net (code "38") (name "Net-(5V_IND-PadA)") (class "Default")
      (node (ref "5V_IND") (pin "A") (pinfunction "A_A") (pintype "passive"))
      (node (ref "R24") (pin "1") (pinfunction "1_1") (pintype "passive"))
    )
    (net (code "39") (name "Net-(ASS_TRIP-D)") (class "Default")
      (node (ref "ASS_TRIP") (pin "3") (pinfunction "D_3") (pintype "bidirectional"))
      (node (ref "D2") (pin "A") (pinfunction "A_A") (pintype "passive"))
      (node (ref "K1") (pin "A2") (pinfunction "2_A2") (pintype "passive"))
    )
    (net (code "40") (name "Net-(ASS_TRIP-G)") (class "Default")
      (node (ref "ASS_TRIP") (pin "1") (pinfunction "G_1") (pintype "bidirectional"))
      (node (ref "R1") (pin "2") (pinfunction "2_2") (pintype "passive"))
      (node (ref "R2") (pin "2") (pinfunction "2_2") (pintype "passive"))
    )
    (net (code "41") (name "Net-(AUDIO_OUT_TR-G)") (class "Default")
      (node (ref "AUDIO_OUT_TR") (pin "1") (pinfunction "G_1") (pintype "bidirectional"))
      (node (ref "R22") (pin "2") (pinfunction "2_2") (pintype "passive"))
      (node (ref "R23") (pin "2") (pinfunction "2_2") (pintype "passive"))
    )
    (net (code "42") (name "Net-(BR_LIGHTS_TR1-G)") (class "Default")
      (node (ref "BR_LIGHTS_TR1") (pin "1") (pinfunction "G_1") (pintype "bidirectional"))
      (node (ref "R12") (pin "2") (pinfunction "2_2") (pintype "passive"))
      (node (ref "R13") (pin "2") (pinfunction "2_2") (pintype "passive"))
    )
    (net (code "43") (name "Net-(IC4-ADJ)") (class "Default")
      (node (ref "IC4") (pin "1") (pinfunction "ADJ_1") (pintype "input"))
      (node (ref "R7") (pin "1") (pinfunction "1_1") (pintype "passive"))
      (node (ref "R8") (pin "2") (pinfunction "2_2") (pintype "passive"))
    )
    (net (code "44") (name "Net-(U$1-J5002-AREF)") (class "Default")
      (node (ref "U$1") (pin "J5002") (pinfunction "J5002-AREF_J5002") (pintype "bidirectional"))
      (node (ref "U1") (pin "2") (pinfunction "C_2") (pintype "passive"))
    )
    (net (code "45") (name "Net-(U$1-J5031-D6)") (class "Default")
      (node (ref "R1") (pin "1") (pinfunction "1_1") (pintype "passive"))
      (node (ref "U$1") (pin "J5031") (pinfunction "J5031-D6_J5031") (pintype "bidirectional"))
    )
    (net (code "46") (name "Net-(U2A-C1+)") (class "Default")
      (node (ref "C2") (pin "1") (pinfunction "1_1") (pintype "passive"))
      (node (ref "U2") (pin "1") (pinfunction "C1+_1") (pintype "bidirectional"))
    )
    (net (code "47") (name "Net-(U2A-C1-)") (class "Default")
      (node (ref "C2") (pin "2") (pinfunction "2_2") (pintype "passive"))
      (node (ref "U2") (pin "3") (pinfunction "C1-_3") (pintype "bidirectional"))
    )
    (net (code "48") (name "Net-(U2A-C2+)") (class "Default")
      (node (ref "C3") (pin "1") (pinfunction "1_1") (pintype "passive"))
      (node (ref "U2") (pin "4") (pinfunction "C2+_4") (pintype "bidirectional"))
    )
    (net (code "49") (name "Net-(U2A-C2-)") (class "Default")
      (node (ref "C3") (pin "2") (pinfunction "2_2") (pintype "passive"))
      (node (ref "U2") (pin "5") (pinfunction "C2-_5") (pintype "bidirectional"))
    )
    (net (code "50") (name "Net-(U2A-R1OUT)") (class "Default")
      (node (ref "JP3") (pin "1") (pinfunction "1_1") (pintype "passive"))
      (node (ref "U2") (pin "12") (pinfunction "R1OUT_12") (pintype "output"))
    )
    (net (code "51") (name "Net-(U2A-R2OUT)") (class "Default")
      (node (ref "JP4") (pin "1") (pinfunction "1_1") (pintype "passive"))
      (node (ref "U2") (pin "9") (pinfunction "R2OUT_9") (pintype "output"))
    )
    (net (code "52") (name "Net-(U2A-T1IN)") (class "Default")
      (node (ref "JP1") (pin "1") (pinfunction "1_1") (pintype "passive"))
      (node (ref "U2") (pin "11") (pinfunction "T1IN_11") (pintype "input"))
    )
    (net (code "53") (name "Net-(U2A-T2IN)") (class "Default")
      (node (ref "JP2") (pin "1") (pinfunction "1_1") (pintype "passive"))
      (node (ref "U2") (pin "10") (pinfunction "T2IN_10") (pintype "input"))
    )
    (net (code "54") (name "Net-(U2A-V+)") (class "Default")
      (node (ref "C4") (pin "1") (pinfunction "1_1") (pintype "passive"))
      (node (ref "U2") (pin "2") (pinfunction "V+_2") (pintype "bidirectional"))
    )
    (net (code "55") (name "Net-(U2A-V-)") (class "Default")
      (node (ref "C9") (pin "1") (pinfunction "1_1") (pintype "passive"))
      (node (ref "U2") (pin "6") (pinfunction "V-_6") (pintype "bidirectional"))
    )
    (net (code "56") (name "Net-(U3A--IN)") (class "Default")
      (node (ref "R15") (pin "2") (pinfunction "2_2") (pintype "passive"))
      (node (ref "U3") (pin "1") (pinfunction "OUT_1") (pintype "output"))
      (node (ref "U3") (pin "2") (pinfunction "-IN_2") (pintype "input"))
    )
    (net (code "57") (name "Net-(U3B--IN)") (class "Default")
      (node (ref "R10") (pin "2") (pinfunction "2_2") (pintype "passive"))
      (node (ref "U3") (pin "8") (pinfunction "OUT_8") (pintype "output"))
      (node (ref "U3") (pin "9") (pinfunction "-IN_9") (pintype "input"))
    )
    (net (code "58") (name "Net-(U3C--IN)") (class "Default")
      (node (ref "R6") (pin "2") (pinfunction "2_2") (pintype "passive"))
      (node (ref "U3") (pin "6") (pinfunction "-IN_6") (pintype "input"))
      (node (ref "U3") (pin "7") (pinfunction "OUT_7") (pintype "output"))
    )
    (net (code "59") (name "Net-(U3D--IN)") (class "Default")
      (node (ref "R4") (pin "2") (pinfunction "2_2") (pintype "passive"))
      (node (ref "U3") (pin "13") (pinfunction "-IN_13") (pintype "input"))
      (node (ref "U3") (pin "14") (pinfunction "OUT_14") (pintype "output"))
    )
    (net (code "60") (name "PRESSURE_L_SIG_IN") (class "Default")
      (node (ref "R14") (pin "2") (pinfunction "2_2") (pintype "passive"))
      (node (ref "R15") (pin "1") (pinfunction "1_1") (pintype "passive"))
      (node (ref "U$1") (pin "J5072") (pinfunction "J5072-D24_J5072") (pintype "bidirectional"))
    )
    (net (code "61") (name "PRESSURE_L_SIG_IN_UNREG") (class "Default")
      (node (ref "J6") (pin "3") (pinfunction "3_3") (pintype "bidirectional"))
      (node (ref "U3") (pin "3") (pinfunction "+IN_3") (pintype "input"))
    )
    (net (code "62") (name "PRESSURE_L_SIG_OUT") (class "Default")
      (node (ref "R5") (pin "2") (pinfunction "2_2") (pintype "passive"))
      (node (ref "R6") (pin "1") (pinfunction "1_1") (pintype "passive"))
      (node (ref "U$1") (pin "J50734") (pinfunction "J50734-D23_J50734") (pintype "bidirectional"))
    )
    (net (code "63") (name "PRESSURE_L_SIG_OUT_UNREG") (class "Default")
      (node (ref "J6") (pin "4") (pinfunction "4_4") (pintype "bidirectional"))
      (node (ref "U3") (pin "5") (pinfunction "+IN_5") (pintype "input"))
    )
    (net (code "64") (name "PRESSURE_R_SIG_IN") (class "Default")
      (node (ref "R3") (pin "2") (pinfunction "2_2") (pintype "passive"))
      (node (ref "R4") (pin "1") (pinfunction "1_1") (pintype "passive"))
      (node (ref "U$1") (pin "J5023") (pinfunction "J5023-AD3_J5023") (pintype "bidirectional"))
    )
    (net (code "65") (name "PRESSURE_R_SIG_IN_UNREG") (class "Default")
      (node (ref "J8") (pin "3") (pinfunction "3_3") (pintype "bidirectional"))
      (node (ref "U3") (pin "12") (pinfunction "+IN_12") (pintype "input"))
    )
    (net (code "66") (name "PRESSURE_R_SIG_OUT") (class "Default")
      (node (ref "R10") (pin "1") (pinfunction "1_1") (pintype "passive"))
      (node (ref "R9") (pin "2") (pinfunction "2_2") (pintype "passive"))
      (node (ref "U$1") (pin "J5022") (pinfunction "J5022-AD2_J5022") (pintype "bidirectional"))
    )
    (net (code "67") (name "PRESSURE_R_SIG_OUT_UNREG") (class "Default")
      (node (ref "J8") (pin "4") (pinfunction "4_4") (pintype "bidirectional"))
      (node (ref "U3") (pin "10") (pinfunction "+IN_10") (pintype "input"))
    )
    (net (code "68") (name "RXD") (class "Default")
      (node (ref "U$1") (pin "J5046") (pinfunction "J5046-CANRX_J5046") (pintype "bidirectional"))
      (node (ref "U$3") (pin "PIN_3") (pinfunction "RXD_PIN_3") (pintype "bidirectional"))
    )
    (net (code "69") (name "TEMP_L_IN") (class "Default")
      (node (ref "J6") (pin "5") (pinfunction "5_5") (pintype "bidirectional"))
      (node (ref "R11") (pin "1") (pinfunction "1_1") (pintype "passive"))
      (node (ref "U$1") (pin "J5027") (pinfunction "J5027-AD7_J5027") (pintype "bidirectional"))
    )
    (net (code "70") (name "TEMP_L_OUT") (class "Default")
      (node (ref "J6") (pin "6") (pinfunction "6_6") (pintype "bidirectional"))
      (node (ref "R16") (pin "1") (pinfunction "1_1") (pintype "passive"))
      (node (ref "U$1") (pin "J5025") (pinfunction "J5025-AD5_J5025") (pintype "bidirectional"))
    )
    (net (code "71") (name "TEMP_R_IN") (class "Default")
      (node (ref "J8") (pin "5") (pinfunction "5_5") (pintype "bidirectional"))
      (node (ref "R17") (pin "1") (pinfunction "1_1") (pintype "passive"))
      (node (ref "U$1") (pin "J5021") (pinfunction "J5021-AD1_J5021") (pintype "bidirectional"))
    )
    (net (code "72") (name "TEMP_R_OUT") (class "Default")
      (node (ref "J8") (pin "6") (pinfunction "6_6") (pintype "bidirectional"))
      (node (ref "R21") (pin "1") (pinfunction "1_1") (pintype "passive"))
      (node (ref "U$1") (pin "J5024") (pinfunction "J5024-AD4_J5024") (pintype "bidirectional"))
    )
    (net (code "73") (name "TSAL_STATE") (class "Default")
      (node (ref "J2") (pin "1") (pinfunction "1_1") (pintype "bidirectional"))
      (node (ref "U$1") (pin "J5074") (pinfunction "J5074-D28_J5074") (pintype "bidirectional"))
    )
    (net (code "74") (name "TXD") (class "Default")
      (node (ref "U$1") (pin "J5047") (pinfunction "J5047-CANTX_J5047") (pintype "bidirectional"))
      (node (ref "U$3") (pin "PIN_0") (pinfunction "TXD_PIN_0") (pintype "bidirectional"))
    )
    (net (code "75") (name "unconnected-(J2-Pad2)") (class "Default")
      (node (ref "J2") (pin "2") (pinfunction "2_2") (pintype "bidirectional"))
    )
    (net (code "76") (name "unconnected-(J3-Pad2)") (class "Default")
      (node (ref "J3") (pin "2") (pinfunction "2_2") (pintype "bidirectional"))
    )
    (net (code "77") (name "unconnected-(J4-Pad2)") (class "Default")
      (node (ref "J4") (pin "2") (pinfunction "2_2") (pintype "bidirectional"))
    )
    (net (code "78") (name "unconnected-(U$1-J506-0-MISO-PadJ506-0)") (class "Default")
      (node (ref "U$1") (pin "J506-0") (pinfunction "J506-0-MISO_J506-0") (pintype "bidirectional"))
    )
    (net (code "79") (name "unconnected-(U$1-J506-1-SCK-PadJ506-1)") (class "Default")
      (node (ref "U$1") (pin "J506-1") (pinfunction "J506-1-SCK_J506-1") (pintype "bidirectional"))
    )
    (net (code "80") (name "unconnected-(U$1-J506-2-RST-PadJ506-2)") (class "Default")
      (node (ref "U$1") (pin "J506-2") (pinfunction "J506-2-RST_J506-2") (pintype "bidirectional"))
    )
    (net (code "81") (name "unconnected-(U$1-J506-3-GND-PadJ506-3)") (class "Default")
      (node (ref "U$1") (pin "J506-3") (pinfunction "J506-3-GND_J506-3") (pintype "bidirectional"))
    )
    (net (code "82") (name "unconnected-(U$1-J506-4-MOSI-PadJ506-4)") (class "Default")
      (node (ref "U$1") (pin "J506-4") (pinfunction "J506-4-MOSI_J506-4") (pintype "bidirectional"))
    )
    (net (code "83") (name "unconnected-(U$1-J506-5-5V-PadJ506-5)") (class "Default")
      (node (ref "U$1") (pin "J506-5") (pinfunction "J506-5-5V_J506-5") (pintype "bidirectional"))
    )
    (net (code "84") (name "unconnected-(U$1-J5000-SCL-PadJ5000)") (class "Default")
      (node (ref "U$1") (pin "J5000") (pinfunction "J5000-SCL_J5000") (pintype "bidirectional"))
    )
    (net (code "85") (name "unconnected-(U$1-J5001-SDA-PadJ5001)") (class "Default")
      (node (ref "U$1") (pin "J5001") (pinfunction "J5001-SDA_J5001") (pintype "bidirectional"))
    )
    (net (code "86") (name "unconnected-(U$1-J5003-GND-PadJ5003)") (class "Default")
      (node (ref "U$1") (pin "J5003") (pinfunction "J5003-GND_J5003") (pintype "bidirectional"))
    )
    (net (code "87") (name "unconnected-(U$1-J5004-D13-PadJ5004)") (class "Default")
      (node (ref "U$1") (pin "J5004") (pinfunction "J5004-D13_J5004") (pintype "bidirectional"))
    )
    (net (code "88") (name "unconnected-(U$1-J5005-D12-PadJ5005)") (class "Default")
      (node (ref "U$1") (pin "J5005") (pinfunction "J5005-D12_J5005") (pintype "bidirectional"))
    )
    (net (code "89") (name "unconnected-(U$1-J5006-D11-PadJ5006)") (class "Default")
      (node (ref "U$1") (pin "J5006") (pinfunction "J5006-D11_J5006") (pintype "bidirectional"))
    )
    (net (code "90") (name "unconnected-(U$1-J5009-D8-PadJ5009)") (class "Default")
      (node (ref "U$1") (pin "J5009") (pinfunction "J5009-D8_J5009") (pintype "bidirectional"))
    )
    (net (code "91") (name "unconnected-(U$1-J5010-VBAT-PadJ5010)") (class "Default")
      (node (ref "U$1") (pin "J5010") (pinfunction "J5010-VBAT_J5010") (pintype "bidirectional"))
    )
    (net (code "92") (name "unconnected-(U$1-J5011-IOREF-PadJ5011)") (class "Default")
      (node (ref "U$1") (pin "J5011") (pinfunction "J5011-IOREF_J5011") (pintype "bidirectional"))
    )
    (net (code "93") (name "unconnected-(U$1-J5012-RESET-PadJ5012)") (class "Default")
      (node (ref "U$1") (pin "J5012") (pinfunction "J5012-RESET_J5012") (pintype "bidirectional"))
    )
    (net (code "94") (name "unconnected-(U$1-J5017-VIN-PadJ5017)") (class "Default")
      (node (ref "U$1") (pin "J5017") (pinfunction "J5017-VIN_J5017") (pintype "bidirectional"))
    )
    (net (code "95") (name "unconnected-(U$1-J5033-D4-PadJ5033)") (class "Default")
      (node (ref "U$1") (pin "J5033") (pinfunction "J5033-D4_J5033") (pintype "bidirectional"))
    )
    (net (code "96") (name "unconnected-(U$1-J5036-D1(TXD)-PadJ5036)") (class "Default")
      (node (ref "U$1") (pin "J5036") (pinfunction "J5036-D1(TXD)_J5036") (pintype "bidirectional"))
    )
    (net (code "97") (name "unconnected-(U$1-J5037-D0(RXD)-PadJ5037)") (class "Default")
      (node (ref "U$1") (pin "J5037") (pinfunction "J5037-D0(RXD)_J5037") (pintype "bidirectional"))
    )
    (net (code "98") (name "unconnected-(U$1-J5040-AD8-PadJ5040)") (class "Default")
      (node (ref "U$1") (pin "J5040") (pinfunction "J5040-AD8_J5040") (pintype "bidirectional"))
    )
    (net (code "99") (name "unconnected-(U$1-J5041-AD9-PadJ5041)") (class "Default")
      (node (ref "U$1") (pin "J5041") (pinfunction "J5041-AD9_J5041") (pintype "bidirectional"))
    )
    (net (code "100") (name "unconnected-(U$1-J5042-AD10-PadJ5042)") (class "Default")
      (node (ref "U$1") (pin "J5042") (pinfunction "J5042-AD10_J5042") (pintype "bidirectional"))
    )
    (net (code "101") (name "unconnected-(U$1-J5043-AD11-PadJ5043)") (class "Default")
      (node (ref "U$1") (pin "J5043") (pinfunction "J5043-AD11_J5043") (pintype "bidirectional"))
    )
    (net (code "102") (name "unconnected-(U$1-J5050-D14-PadJ5050)") (class "Default")
      (node (ref "U$1") (pin "J5050") (pinfunction "J5050-D14_J5050") (pintype "bidirectional"))
    )
    (net (code "103") (name "unconnected-(U$1-J5051-D15-PadJ5051)") (class "Default")
      (node (ref "U$1") (pin "J5051") (pinfunction "J5051-D15_J5051") (pintype "bidirectional"))
    )
    (net (code "104") (name "unconnected-(U$1-J5052-D16-PadJ5052)") (class "Default")
      (node (ref "U$1") (pin "J5052") (pinfunction "J5052-D16_J5052") (pintype "bidirectional"))
    )
    (net (code "105") (name "unconnected-(U$1-J5053-D17-PadJ5053)") (class "Default")
      (node (ref "U$1") (pin "J5053") (pinfunction "J5053-D17_J5053") (pintype "bidirectional"))
    )
    (net (code "106") (name "unconnected-(U$1-J5054-D18-PadJ5054)") (class "Default")
      (node (ref "U$1") (pin "J5054") (pinfunction "J5054-D18_J5054") (pintype "bidirectional"))
    )
    (net (code "107") (name "unconnected-(U$1-J5055-D19-PadJ5055)") (class "Default")
      (node (ref "U$1") (pin "J5055") (pinfunction "J5055-D19_J5055") (pintype "bidirectional"))
    )
    (net (code "108") (name "unconnected-(U$1-J5056-D20-PadJ5056)") (class "Default")
      (node (ref "U$1") (pin "J5056") (pinfunction "J5056-D20_J5056") (pintype "bidirectional"))
    )
    (net (code "109") (name "unconnected-(U$1-J5057-D21-PadJ5057)") (class "Default")
      (node (ref "U$1") (pin "J5057") (pinfunction "J5057-D21_J5057") (pintype "bidirectional"))
    )
    (net (code "110") (name "unconnected-(U$1-J5070-5V0-PadJ5070)") (class "Default")
      (node (ref "U$1") (pin "J5070") (pinfunction "J5070-5V0_J5070") (pintype "bidirectional"))
    )
    (net (code "111") (name "unconnected-(U$1-J5071-D22-PadJ5071)") (class "Default")
      (node (ref "U$1") (pin "J5071") (pinfunction "J5071-D22_J5071") (pintype "bidirectional"))
    )
    (net (code "112") (name "unconnected-(U$1-J5075-D30-PadJ5075)") (class "Default")
      (node (ref "U$1") (pin "J5075") (pinfunction "J5075-D30_J5075") (pintype "bidirectional"))
    )
    (net (code "113") (name "unconnected-(U$1-J5076-D32-PadJ5076)") (class "Default")
      (node (ref "U$1") (pin "J5076") (pinfunction "J5076-D32_J5076") (pintype "bidirectional"))
    )
    (net (code "114") (name "unconnected-(U$1-J5077-D34-PadJ5077)") (class "Default")
      (node (ref "U$1") (pin "J5077") (pinfunction "J5077-D34_J5077") (pintype "bidirectional"))
    )
    (net (code "115") (name "unconnected-(U$1-J5078-D36-PadJ5078)") (class "Default")
      (node (ref "U$1") (pin "J5078") (pinfunction "J5078-D36_J5078") (pintype "bidirectional"))
    )
    (net (code "116") (name "unconnected-(U$1-J5079-D38-PadJ5079)") (class "Default")
      (node (ref "U$1") (pin "J5079") (pinfunction "J5079-D38_J5079") (pintype "bidirectional"))
    )
    (net (code "117") (name "unconnected-(U$1-J50710-D40-PadJ50710)") (class "Default")
      (node (ref "U$1") (pin "J50710") (pinfunction "J50710-D40_J50710") (pintype "bidirectional"))
    )
    (net (code "118") (name "unconnected-(U$1-J50711-D42-PadJ50711)") (class "Default")
      (node (ref "U$1") (pin "J50711") (pinfunction "J50711-D42_J50711") (pintype "bidirectional"))
    )
    (net (code "119") (name "unconnected-(U$1-J50712-D44-PadJ50712)") (class "Default")
      (node (ref "U$1") (pin "J50712") (pinfunction "J50712-D44_J50712") (pintype "bidirectional"))
    )
    (net (code "120") (name "unconnected-(U$1-J50714-D48-PadJ50714)") (class "Default")
      (node (ref "U$1") (pin "J50714") (pinfunction "J50714-D48_J50714") (pintype "bidirectional"))
    )
    (net (code "121") (name "unconnected-(U$1-J50715-D50-PadJ50715)") (class "Default")
      (node (ref "U$1") (pin "J50715") (pinfunction "J50715-D50_J50715") (pintype "bidirectional"))
    )
    (net (code "122") (name "unconnected-(U$1-J50716-D52-PadJ50716)") (class "Default")
      (node (ref "U$1") (pin "J50716") (pinfunction "J50716-D52_J50716") (pintype "bidirectional"))
    )
    (net (code "123") (name "unconnected-(U$1-J50717-GND-PadJ50717)") (class "Default")
      (node (ref "U$1") (pin "J50717") (pinfunction "J50717-GND_J50717") (pintype "bidirectional"))
    )
    (net (code "124") (name "unconnected-(U$1-J50718-GND-PadJ50718)") (class "Default")
      (node (ref "U$1") (pin "J50718") (pinfunction "J50718-GND_J50718") (pintype "bidirectional"))
    )
    (net (code "125") (name "unconnected-(U$1-J50719-D53-PadJ50719)") (class "Default")
      (node (ref "U$1") (pin "J50719") (pinfunction "J50719-D53_J50719") (pintype "bidirectional"))
    )
    (net (code "126") (name "unconnected-(U$1-J50720-D51-PadJ50720)") (class "Default")
      (node (ref "U$1") (pin "J50720") (pinfunction "J50720-D51_J50720") (pintype "bidirectional"))
    )
    (net (code "127") (name "unconnected-(U$1-J50721-D49-PadJ50721)") (class "Default")
      (node (ref "U$1") (pin "J50721") (pinfunction "J50721-D49_J50721") (pintype "bidirectional"))
    )
    (net (code "128") (name "unconnected-(U$1-J50722-D47-PadJ50722)") (class "Default")
      (node (ref "U$1") (pin "J50722") (pinfunction "J50722-D47_J50722") (pintype "bidirectional"))
    )
    (net (code "129") (name "unconnected-(U$1-J50723-D45-PadJ50723)") (class "Default")
      (node (ref "U$1") (pin "J50723") (pinfunction "J50723-D45_J50723") (pintype "bidirectional"))
    )
    (net (code "130") (name "unconnected-(U$1-J50724-D43-PadJ50724)") (class "Default")
      (node (ref "U$1") (pin "J50724") (pinfunction "J50724-D43_J50724") (pintype "bidirectional"))
    )
    (net (code "131") (name "unconnected-(U$1-J50725-D41-PadJ50725)") (class "Default")
      (node (ref "U$1") (pin "J50725") (pinfunction "J50725-D41_J50725") (pintype "bidirectional"))
    )
    (net (code "132") (name "unconnected-(U$1-J50726-D39-PadJ50726)") (class "Default")
      (node (ref "U$1") (pin "J50726") (pinfunction "J50726-D39_J50726") (pintype "bidirectional"))
    )
    (net (code "133") (name "unconnected-(U$1-J50727-D37-PadJ50727)") (class "Default")
      (node (ref "U$1") (pin "J50727") (pinfunction "J50727-D37_J50727") (pintype "bidirectional"))
    )
    (net (code "134") (name "unconnected-(U$1-J50728-D35-PadJ50728)") (class "Default")
      (node (ref "U$1") (pin "J50728") (pinfunction "J50728-D35_J50728") (pintype "bidirectional"))
    )
    (net (code "135") (name "unconnected-(U$1-J50729-D33-PadJ50729)") (class "Default")
      (node (ref "U$1") (pin "J50729") (pinfunction "J50729-D33_J50729") (pintype "bidirectional"))
    )
    (net (code "136") (name "unconnected-(U$1-J50730-D31-PadJ50730)") (class "Default")
      (node (ref "U$1") (pin "J50730") (pinfunction "J50730-D31_J50730") (pintype "bidirectional"))
    )
    (net (code "137") (name "unconnected-(U$1-J50731-D29-PadJ50731)") (class "Default")
      (node (ref "U$1") (pin "J50731") (pinfunction "J50731-D29_J50731") (pintype "bidirectional"))
    )
    (net (code "138") (name "unconnected-(U$1-J50735-5V0-PadJ50735)") (class "Default")
      (node (ref "U$1") (pin "J50735") (pinfunction "J50735-5V0_J50735") (pintype "bidirectional"))
    )
    (net (code "139") (name "unconnected-(X2A-F-Pad1)") (class "Default")
      (node (ref "X2") (pin "1") (pinfunction "F_1") (pintype "passive"))
    )
    (net (code "140") (name "unconnected-(X2D-F-Pad4)") (class "Default")
      (node (ref "X2") (pin "4") (pinfunction "F_4") (pintype "passive"))
    )
    (net (code "141") (name "unconnected-(X2E-F-Pad5)") (class "Default")
      (node (ref "X2") (pin "5") (pinfunction "F_5") (pintype "passive"))
    )
    (net (code "142") (name "unconnected-(X2H-F-Pad8)") (class "Default")
      (node (ref "X2") (pin "8") (pinfunction "F_8") (pintype "passive"))
    )
  )
)
